# 15-DPLL_2.net
KiCad netlist of a schematic drawn in Altium Designer
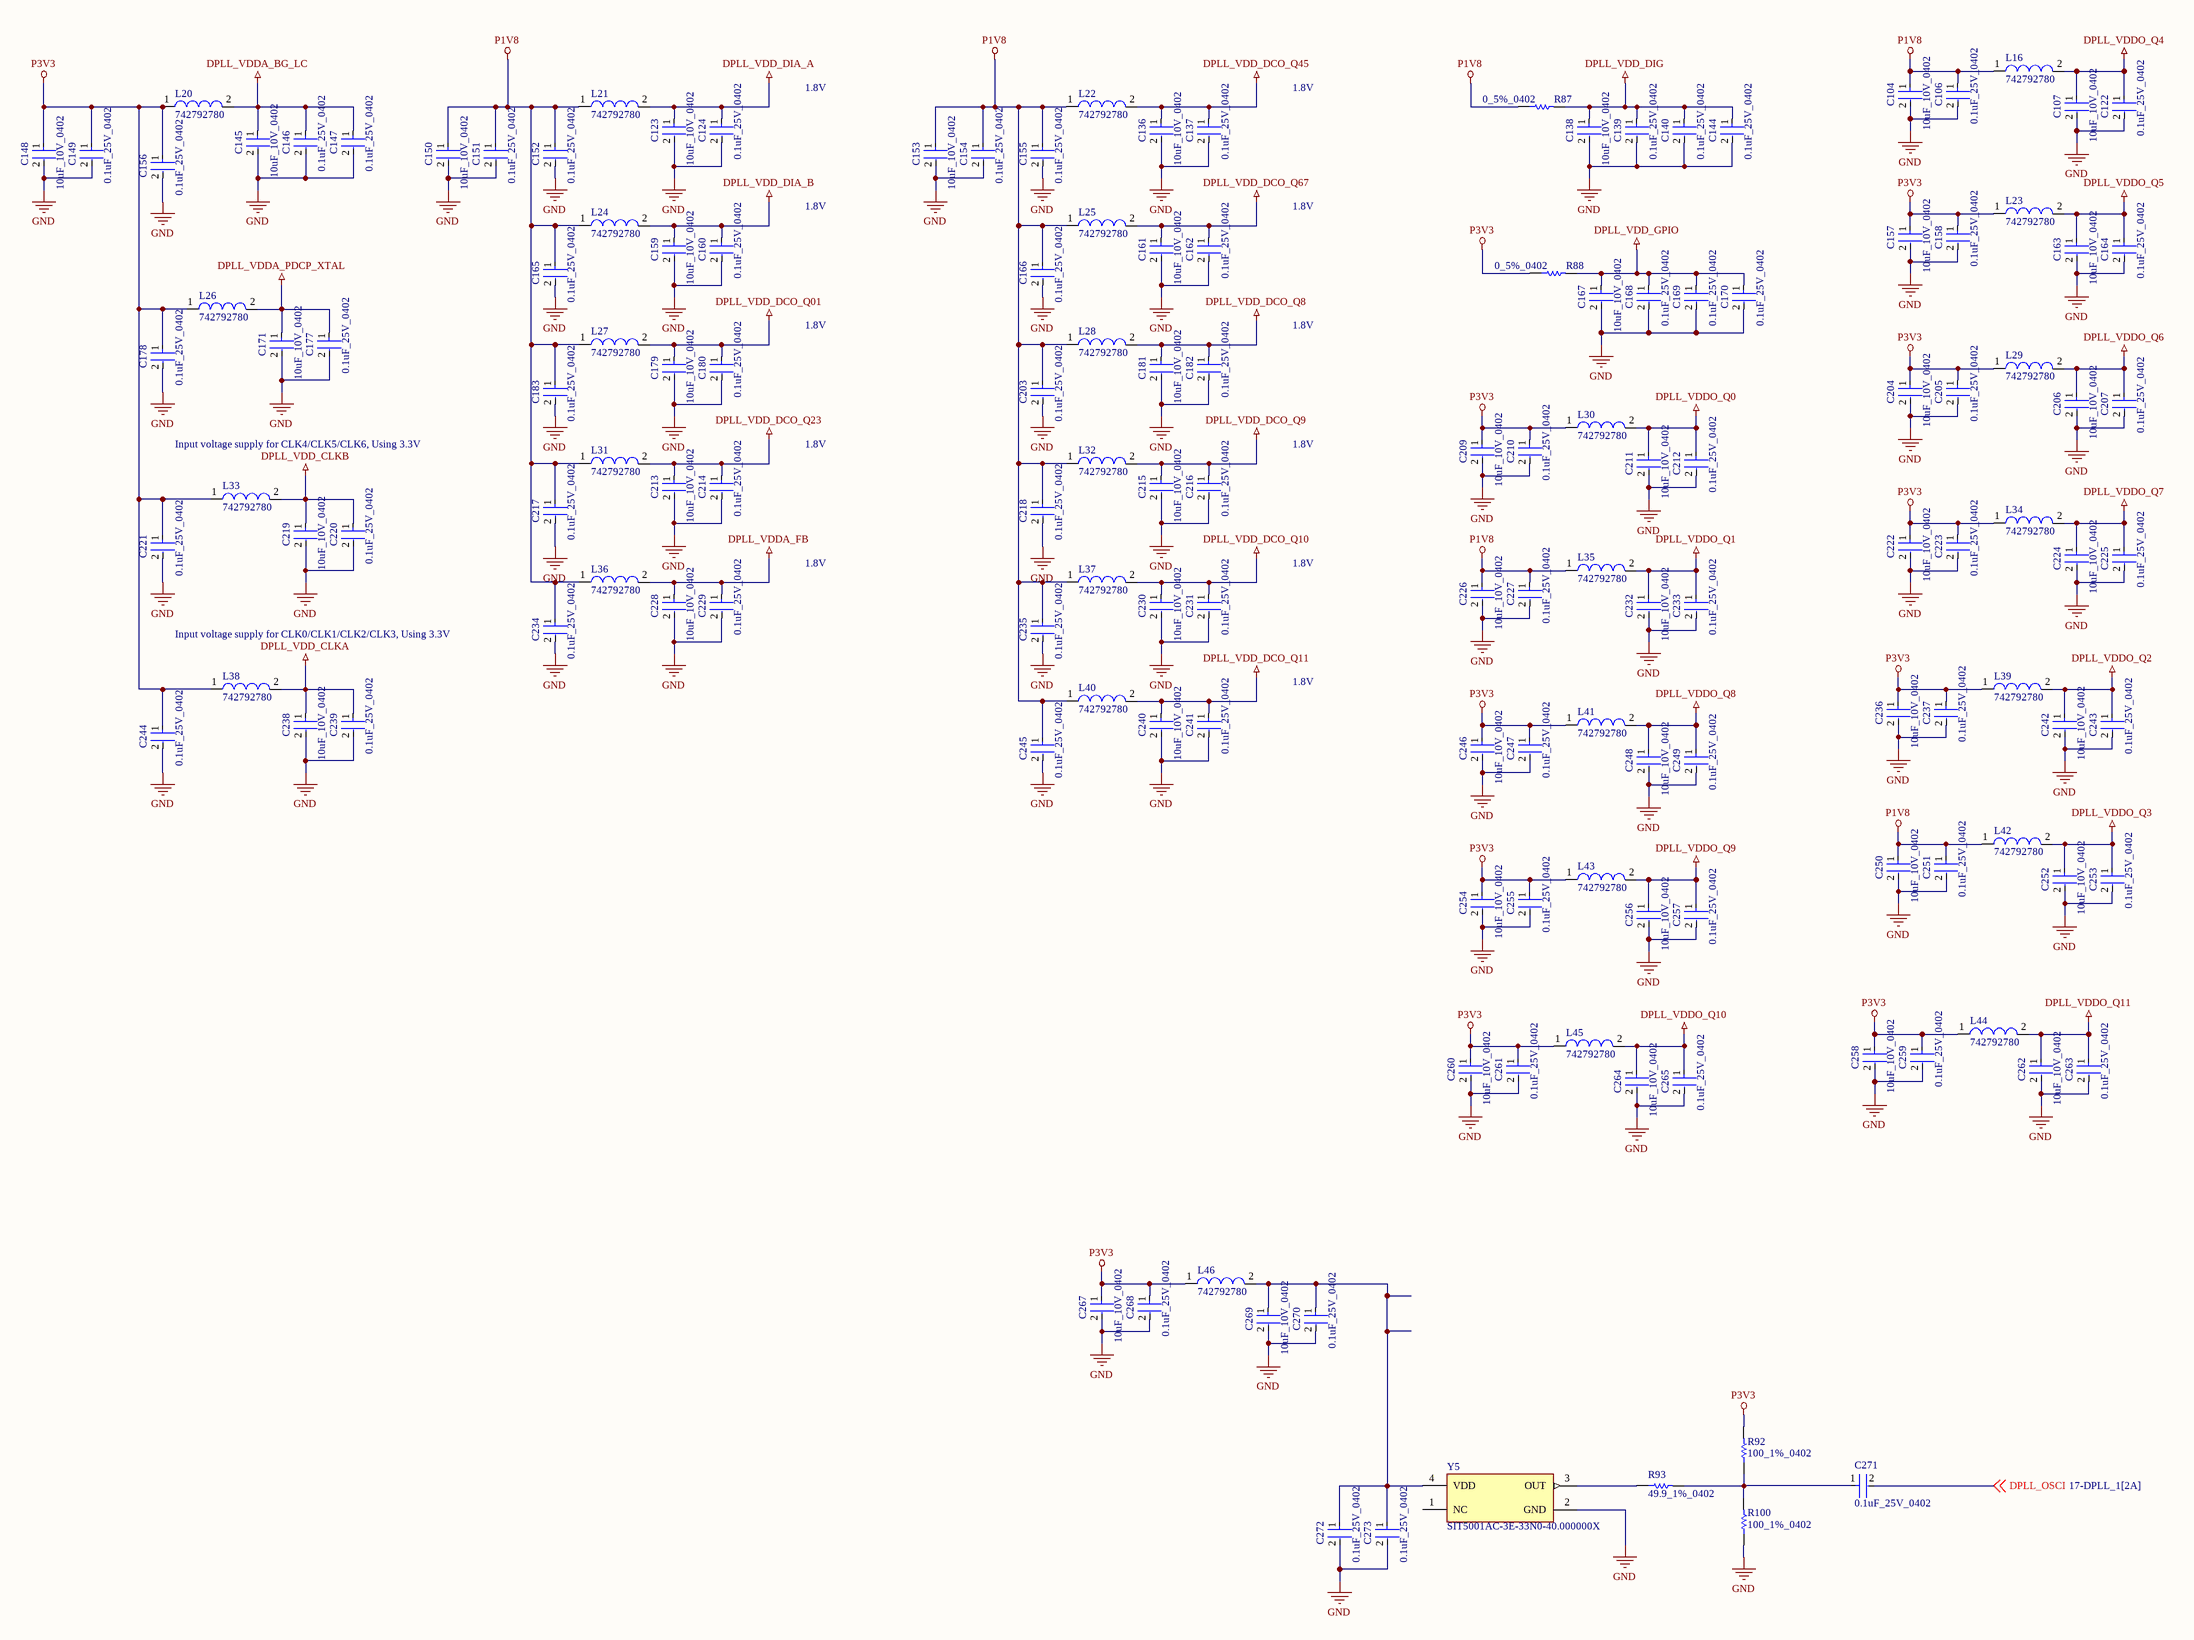
[diagram p0: 15-DPLL_2.SchDoc]

(export (version "E")
  (design (tool "Eeschema 10.0.6"))
  (components
    (comp (ref "C104")
      (value "10uF_10V_0402")
      (footprint "FP-CL05A106MP5NUNC-MFG")
      (description "CAP CER 10UF 10V X5R 0402")
      (fields
        (field (name "OCTOPART") "https://octopart.com/cl05a106mp5nunc-samsung-22457395")
        (field (name "TOLERANCE") "20%")
      )
      (libsource (lib "Altium Content Vault") (part "b4654b650e69147ec39a6b967a45e02"))
    )
    (comp (ref "C106")
      (value "0.1uF_25V_0402")
      (footprint "FP-0402-L_1_0_1-W_0_5_0_1-IPC_C")
      (description "General Purpose Ceramic Capacitor, 0402, 100nF, 10%, X7R, 15%, 25V")
      (fields (field (name "VOLTAGE") "25V") (field (name "TOLERANCE") "10%"))
      (libsource (lib "Altium Content Vault") (part "b4654b650e69147ec39a6b967a45e02"))
    )
    (comp (ref "C107")
      (value "10uF_10V_0402")
      (footprint "FP-CL05A106MP5NUNC-MFG")
      (description "CAP CER 10UF 10V X5R 0402")
      (fields
        (field (name "OCTOPART") "https://octopart.com/cl05a106mp5nunc-samsung-22457395")
        (field (name "TOLERANCE") "20%")
      )
      (libsource (lib "Altium Content Vault") (part "b4654b650e69147ec39a6b967a45e02"))
    )
    (comp (ref "C122")
      (value "0.1uF_25V_0402")
      (footprint "FP-0402-L_1_0_1-W_0_5_0_1-IPC_C")
      (description "General Purpose Ceramic Capacitor, 0402, 100nF, 10%, X7R, 15%, 25V")
      (fields (field (name "VOLTAGE") "25V") (field (name "TOLERANCE") "10%"))
      (libsource (lib "Altium Content Vault") (part "b4654b650e69147ec39a6b967a45e02"))
    )
    (comp (ref "C123")
      (value "10uF_10V_0402")
      (footprint "FP-CL05A106MP5NUNC-MFG")
      (description "CAP CER 10UF 10V X5R 0402")
      (fields
        (field (name "OCTOPART") "https://octopart.com/cl05a106mp5nunc-samsung-22457395")
        (field (name "TOLERANCE") "20%")
      )
      (libsource (lib "Altium Content Vault") (part "b4654b650e69147ec39a6b967a45e02"))
    )
    (comp (ref "C124")
      (value "0.1uF_25V_0402")
      (footprint "FP-0402-L_1_0_1-W_0_5_0_1-IPC_C")
      (description "General Purpose Ceramic Capacitor, 0402, 100nF, 10%, X7R, 15%, 25V")
      (fields (field (name "VOLTAGE") "25V") (field (name "TOLERANCE") "10%"))
      (libsource (lib "Altium Content Vault") (part "b4654b650e69147ec39a6b967a45e02"))
    )
    (comp (ref "C136")
      (value "10uF_10V_0402")
      (footprint "FP-CL05A106MP5NUNC-MFG")
      (description "CAP CER 10UF 10V X5R 0402")
      (fields
        (field (name "OCTOPART") "https://octopart.com/cl05a106mp5nunc-samsung-22457395")
        (field (name "TOLERANCE") "20%")
      )
      (libsource (lib "Altium Content Vault") (part "b4654b650e69147ec39a6b967a45e02"))
    )
    (comp (ref "C137")
      (value "0.1uF_25V_0402")
      (footprint "FP-0402-L_1_0_1-W_0_5_0_1-IPC_C")
      (description "General Purpose Ceramic Capacitor, 0402, 100nF, 10%, X7R, 15%, 25V")
      (fields (field (name "VOLTAGE") "25V") (field (name "TOLERANCE") "10%"))
      (libsource (lib "Altium Content Vault") (part "b4654b650e69147ec39a6b967a45e02"))
    )
    (comp (ref "C138")
      (value "10uF_10V_0402")
      (footprint "FP-CL05A106MP5NUNC-MFG")
      (description "CAP CER 10UF 10V X5R 0402")
      (fields
        (field (name "OCTOPART") "https://octopart.com/cl05a106mp5nunc-samsung-22457395")
        (field (name "TOLERANCE") "20%")
      )
      (libsource (lib "Altium Content Vault") (part "b4654b650e69147ec39a6b967a45e02"))
    )
    (comp (ref "C139")
      (value "0.1uF_25V_0402")
      (footprint "FP-0402-L_1_0_1-W_0_5_0_1-IPC_C")
      (description "General Purpose Ceramic Capacitor, 0402, 100nF, 10%, X7R, 15%, 25V")
      (fields (field (name "VOLTAGE") "25V") (field (name "TOLERANCE") "10%"))
      (libsource (lib "Altium Content Vault") (part "b4654b650e69147ec39a6b967a45e02"))
    )
    (comp (ref "C140")
      (value "0.1uF_25V_0402")
      (footprint "FP-0402-L_1_0_1-W_0_5_0_1-IPC_C")
      (description "General Purpose Ceramic Capacitor, 0402, 100nF, 10%, X7R, 15%, 25V")
      (fields (field (name "VOLTAGE") "25V") (field (name "TOLERANCE") "10%"))
      (libsource (lib "Altium Content Vault") (part "b4654b650e69147ec39a6b967a45e02"))
    )
    (comp (ref "C144")
      (value "0.1uF_25V_0402")
      (footprint "FP-0402-L_1_0_1-W_0_5_0_1-IPC_C")
      (description "General Purpose Ceramic Capacitor, 0402, 100nF, 10%, X7R, 15%, 25V")
      (fields (field (name "VOLTAGE") "25V") (field (name "TOLERANCE") "10%"))
      (libsource (lib "Altium Content Vault") (part "b4654b650e69147ec39a6b967a45e02"))
    )
    (comp (ref "C145")
      (value "10uF_10V_0402")
      (footprint "FP-CL05A106MP5NUNC-MFG")
      (description "CAP CER 10UF 10V X5R 0402")
      (fields
        (field (name "OCTOPART") "https://octopart.com/cl05a106mp5nunc-samsung-22457395")
        (field (name "TOLERANCE") "20%")
      )
      (libsource (lib "Altium Content Vault") (part "b4654b650e69147ec39a6b967a45e02"))
    )
    (comp (ref "C146")
      (value "0.1uF_25V_0402")
      (footprint "FP-0402-L_1_0_1-W_0_5_0_1-IPC_C")
      (description "General Purpose Ceramic Capacitor, 0402, 100nF, 10%, X7R, 15%, 25V")
      (fields (field (name "VOLTAGE") "25V") (field (name "TOLERANCE") "10%"))
      (libsource (lib "Altium Content Vault") (part "b4654b650e69147ec39a6b967a45e02"))
    )
    (comp (ref "C147")
      (value "0.1uF_25V_0402")
      (footprint "FP-0402-L_1_0_1-W_0_5_0_1-IPC_C")
      (description "General Purpose Ceramic Capacitor, 0402, 100nF, 10%, X7R, 15%, 25V")
      (fields (field (name "VOLTAGE") "25V") (field (name "TOLERANCE") "10%"))
      (libsource (lib "Altium Content Vault") (part "b4654b650e69147ec39a6b967a45e02"))
    )
    (comp (ref "C148")
      (value "10uF_10V_0402")
      (footprint "FP-CL05A106MP5NUNC-MFG")
      (description "CAP CER 10UF 10V X5R 0402")
      (fields
        (field (name "OCTOPART") "https://octopart.com/cl05a106mp5nunc-samsung-22457395")
        (field (name "TOLERANCE") "20%")
      )
      (libsource (lib "Altium Content Vault") (part "b4654b650e69147ec39a6b967a45e02"))
    )
    (comp (ref "C149")
      (value "0.1uF_25V_0402")
      (footprint "FP-0402-L_1_0_1-W_0_5_0_1-IPC_C")
      (description "General Purpose Ceramic Capacitor, 0402, 100nF, 10%, X7R, 15%, 25V")
      (fields (field (name "VOLTAGE") "25V") (field (name "TOLERANCE") "10%"))
      (libsource (lib "Altium Content Vault") (part "b4654b650e69147ec39a6b967a45e02"))
    )
    (comp (ref "C150")
      (value "10uF_10V_0402")
      (footprint "FP-CL05A106MP5NUNC-MFG")
      (description "CAP CER 10UF 10V X5R 0402")
      (fields
        (field (name "OCTOPART") "https://octopart.com/cl05a106mp5nunc-samsung-22457395")
        (field (name "TOLERANCE") "20%")
      )
      (libsource (lib "Altium Content Vault") (part "b4654b650e69147ec39a6b967a45e02"))
    )
    (comp (ref "C151")
      (value "0.1uF_25V_0402")
      (footprint "FP-0402-L_1_0_1-W_0_5_0_1-IPC_C")
      (description "General Purpose Ceramic Capacitor, 0402, 100nF, 10%, X7R, 15%, 25V")
      (fields (field (name "VOLTAGE") "25V") (field (name "TOLERANCE") "10%"))
      (libsource (lib "Altium Content Vault") (part "b4654b650e69147ec39a6b967a45e02"))
    )
    (comp (ref "C152")
      (value "0.1uF_25V_0402")
      (footprint "FP-0402-L_1_0_1-W_0_5_0_1-IPC_C")
      (description "General Purpose Ceramic Capacitor, 0402, 100nF, 10%, X7R, 15%, 25V")
      (fields (field (name "VOLTAGE") "25V") (field (name "TOLERANCE") "10%"))
      (libsource (lib "Altium Content Vault") (part "b4654b650e69147ec39a6b967a45e02"))
    )
    (comp (ref "C153")
      (value "10uF_10V_0402")
      (footprint "FP-CL05A106MP5NUNC-MFG")
      (description "CAP CER 10UF 10V X5R 0402")
      (fields
        (field (name "OCTOPART") "https://octopart.com/cl05a106mp5nunc-samsung-22457395")
        (field (name "TOLERANCE") "20%")
      )
      (libsource (lib "Altium Content Vault") (part "b4654b650e69147ec39a6b967a45e02"))
    )
    (comp (ref "C154")
      (value "0.1uF_25V_0402")
      (footprint "FP-0402-L_1_0_1-W_0_5_0_1-IPC_C")
      (description "General Purpose Ceramic Capacitor, 0402, 100nF, 10%, X7R, 15%, 25V")
      (fields (field (name "VOLTAGE") "25V") (field (name "TOLERANCE") "10%"))
      (libsource (lib "Altium Content Vault") (part "b4654b650e69147ec39a6b967a45e02"))
    )
    (comp (ref "C155")
      (value "0.1uF_25V_0402")
      (footprint "FP-0402-L_1_0_1-W_0_5_0_1-IPC_C")
      (description "General Purpose Ceramic Capacitor, 0402, 100nF, 10%, X7R, 15%, 25V")
      (fields (field (name "VOLTAGE") "25V") (field (name "TOLERANCE") "10%"))
      (libsource (lib "Altium Content Vault") (part "b4654b650e69147ec39a6b967a45e02"))
    )
    (comp (ref "C156")
      (value "0.1uF_25V_0402")
      (footprint "FP-0402-L_1_0_1-W_0_5_0_1-IPC_C")
      (description "General Purpose Ceramic Capacitor, 0402, 100nF, 10%, X7R, 15%, 25V")
      (fields (field (name "VOLTAGE") "25V") (field (name "TOLERANCE") "10%"))
      (libsource (lib "Altium Content Vault") (part "b4654b650e69147ec39a6b967a45e02"))
    )
    (comp (ref "C157")
      (value "10uF_10V_0402")
      (footprint "FP-CL05A106MP5NUNC-MFG")
      (description "CAP CER 10UF 10V X5R 0402")
      (fields
        (field (name "OCTOPART") "https://octopart.com/cl05a106mp5nunc-samsung-22457395")
        (field (name "TOLERANCE") "20%")
      )
      (libsource (lib "Altium Content Vault") (part "b4654b650e69147ec39a6b967a45e02"))
    )
    (comp (ref "C158")
      (value "0.1uF_25V_0402")
      (footprint "FP-0402-L_1_0_1-W_0_5_0_1-IPC_C")
      (description "General Purpose Ceramic Capacitor, 0402, 100nF, 10%, X7R, 15%, 25V")
      (fields (field (name "VOLTAGE") "25V") (field (name "TOLERANCE") "10%"))
      (libsource (lib "Altium Content Vault") (part "b4654b650e69147ec39a6b967a45e02"))
    )
    (comp (ref "C159")
      (value "10uF_10V_0402")
      (footprint "FP-CL05A106MP5NUNC-MFG")
      (description "CAP CER 10UF 10V X5R 0402")
      (fields
        (field (name "OCTOPART") "https://octopart.com/cl05a106mp5nunc-samsung-22457395")
        (field (name "TOLERANCE") "20%")
      )
      (libsource (lib "Altium Content Vault") (part "b4654b650e69147ec39a6b967a45e02"))
    )
    (comp (ref "C160")
      (value "0.1uF_25V_0402")
      (footprint "FP-0402-L_1_0_1-W_0_5_0_1-IPC_C")
      (description "General Purpose Ceramic Capacitor, 0402, 100nF, 10%, X7R, 15%, 25V")
      (fields (field (name "VOLTAGE") "25V") (field (name "TOLERANCE") "10%"))
      (libsource (lib "Altium Content Vault") (part "b4654b650e69147ec39a6b967a45e02"))
    )
    (comp (ref "C161")
      (value "10uF_10V_0402")
      (footprint "FP-CL05A106MP5NUNC-MFG")
      (description "CAP CER 10UF 10V X5R 0402")
      (fields
        (field (name "OCTOPART") "https://octopart.com/cl05a106mp5nunc-samsung-22457395")
        (field (name "TOLERANCE") "20%")
      )
      (libsource (lib "Altium Content Vault") (part "b4654b650e69147ec39a6b967a45e02"))
    )
    (comp (ref "C162")
      (value "0.1uF_25V_0402")
      (footprint "FP-0402-L_1_0_1-W_0_5_0_1-IPC_C")
      (description "General Purpose Ceramic Capacitor, 0402, 100nF, 10%, X7R, 15%, 25V")
      (fields (field (name "VOLTAGE") "25V") (field (name "TOLERANCE") "10%"))
      (libsource (lib "Altium Content Vault") (part "b4654b650e69147ec39a6b967a45e02"))
    )
    (comp (ref "C163")
      (value "10uF_10V_0402")
      (footprint "FP-CL05A106MP5NUNC-MFG")
      (description "CAP CER 10UF 10V X5R 0402")
      (fields
        (field (name "OCTOPART") "https://octopart.com/cl05a106mp5nunc-samsung-22457395")
        (field (name "TOLERANCE") "20%")
      )
      (libsource (lib "Altium Content Vault") (part "b4654b650e69147ec39a6b967a45e02"))
    )
    (comp (ref "C164")
      (value "0.1uF_25V_0402")
      (footprint "FP-0402-L_1_0_1-W_0_5_0_1-IPC_C")
      (description "General Purpose Ceramic Capacitor, 0402, 100nF, 10%, X7R, 15%, 25V")
      (fields (field (name "VOLTAGE") "25V") (field (name "TOLERANCE") "10%"))
      (libsource (lib "Altium Content Vault") (part "b4654b650e69147ec39a6b967a45e02"))
    )
    (comp (ref "C165")
      (value "0.1uF_25V_0402")
      (footprint "FP-0402-L_1_0_1-W_0_5_0_1-IPC_C")
      (description "General Purpose Ceramic Capacitor, 0402, 100nF, 10%, X7R, 15%, 25V")
      (fields (field (name "VOLTAGE") "25V") (field (name "TOLERANCE") "10%"))
      (libsource (lib "Altium Content Vault") (part "b4654b650e69147ec39a6b967a45e02"))
    )
    (comp (ref "C166")
      (value "0.1uF_25V_0402")
      (footprint "FP-0402-L_1_0_1-W_0_5_0_1-IPC_C")
      (description "General Purpose Ceramic Capacitor, 0402, 100nF, 10%, X7R, 15%, 25V")
      (fields (field (name "VOLTAGE") "25V") (field (name "TOLERANCE") "10%"))
      (libsource (lib "Altium Content Vault") (part "b4654b650e69147ec39a6b967a45e02"))
    )
    (comp (ref "C167")
      (value "10uF_10V_0402")
      (footprint "FP-CL05A106MP5NUNC-MFG")
      (description "CAP CER 10UF 10V X5R 0402")
      (fields
        (field (name "OCTOPART") "https://octopart.com/cl05a106mp5nunc-samsung-22457395")
        (field (name "TOLERANCE") "20%")
      )
      (libsource (lib "Altium Content Vault") (part "b4654b650e69147ec39a6b967a45e02"))
    )
    (comp (ref "C168")
      (value "0.1uF_25V_0402")
      (footprint "FP-0402-L_1_0_1-W_0_5_0_1-IPC_C")
      (description "General Purpose Ceramic Capacitor, 0402, 100nF, 10%, X7R, 15%, 25V")
      (fields (field (name "VOLTAGE") "25V") (field (name "TOLERANCE") "10%"))
      (libsource (lib "Altium Content Vault") (part "b4654b650e69147ec39a6b967a45e02"))
    )
    (comp (ref "C169")
      (value "0.1uF_25V_0402")
      (footprint "FP-0402-L_1_0_1-W_0_5_0_1-IPC_C")
      (description "General Purpose Ceramic Capacitor, 0402, 100nF, 10%, X7R, 15%, 25V")
      (fields (field (name "VOLTAGE") "25V") (field (name "TOLERANCE") "10%"))
      (libsource (lib "Altium Content Vault") (part "b4654b650e69147ec39a6b967a45e02"))
    )
    (comp (ref "C170")
      (value "0.1uF_25V_0402")
      (footprint "FP-0402-L_1_0_1-W_0_5_0_1-IPC_C")
      (description "General Purpose Ceramic Capacitor, 0402, 100nF, 10%, X7R, 15%, 25V")
      (fields (field (name "VOLTAGE") "25V") (field (name "TOLERANCE") "10%"))
      (libsource (lib "Altium Content Vault") (part "b4654b650e69147ec39a6b967a45e02"))
    )
    (comp (ref "C171")
      (value "10uF_10V_0402")
      (footprint "FP-CL05A106MP5NUNC-MFG")
      (description "CAP CER 10UF 10V X5R 0402")
      (fields
        (field (name "OCTOPART") "https://octopart.com/cl05a106mp5nunc-samsung-22457395")
        (field (name "TOLERANCE") "20%")
      )
      (libsource (lib "Altium Content Vault") (part "b4654b650e69147ec39a6b967a45e02"))
    )
    (comp (ref "C177")
      (value "0.1uF_25V_0402")
      (footprint "FP-0402-L_1_0_1-W_0_5_0_1-IPC_C")
      (description "General Purpose Ceramic Capacitor, 0402, 100nF, 10%, X7R, 15%, 25V")
      (fields (field (name "VOLTAGE") "25V") (field (name "TOLERANCE") "10%"))
      (libsource (lib "Altium Content Vault") (part "b4654b650e69147ec39a6b967a45e02"))
    )
    (comp (ref "C178")
      (value "0.1uF_25V_0402")
      (footprint "FP-0402-L_1_0_1-W_0_5_0_1-IPC_C")
      (description "General Purpose Ceramic Capacitor, 0402, 100nF, 10%, X7R, 15%, 25V")
      (fields (field (name "VOLTAGE") "25V") (field (name "TOLERANCE") "10%"))
      (libsource (lib "Altium Content Vault") (part "b4654b650e69147ec39a6b967a45e02"))
    )
    (comp (ref "C179")
      (value "10uF_10V_0402")
      (footprint "FP-CL05A106MP5NUNC-MFG")
      (description "CAP CER 10UF 10V X5R 0402")
      (fields
        (field (name "OCTOPART") "https://octopart.com/cl05a106mp5nunc-samsung-22457395")
        (field (name "TOLERANCE") "20%")
      )
      (libsource (lib "Altium Content Vault") (part "b4654b650e69147ec39a6b967a45e02"))
    )
    (comp (ref "C180")
      (value "0.1uF_25V_0402")
      (footprint "FP-0402-L_1_0_1-W_0_5_0_1-IPC_C")
      (description "General Purpose Ceramic Capacitor, 0402, 100nF, 10%, X7R, 15%, 25V")
      (fields (field (name "VOLTAGE") "25V") (field (name "TOLERANCE") "10%"))
      (libsource (lib "Altium Content Vault") (part "b4654b650e69147ec39a6b967a45e02"))
    )
    (comp (ref "C181")
      (value "10uF_10V_0402")
      (footprint "FP-CL05A106MP5NUNC-MFG")
      (description "CAP CER 10UF 10V X5R 0402")
      (fields
        (field (name "OCTOPART") "https://octopart.com/cl05a106mp5nunc-samsung-22457395")
        (field (name "TOLERANCE") "20%")
      )
      (libsource (lib "Altium Content Vault") (part "b4654b650e69147ec39a6b967a45e02"))
    )
    (comp (ref "C182")
      (value "0.1uF_25V_0402")
      (footprint "FP-0402-L_1_0_1-W_0_5_0_1-IPC_C")
      (description "General Purpose Ceramic Capacitor, 0402, 100nF, 10%, X7R, 15%, 25V")
      (fields (field (name "VOLTAGE") "25V") (field (name "TOLERANCE") "10%"))
      (libsource (lib "Altium Content Vault") (part "b4654b650e69147ec39a6b967a45e02"))
    )
    (comp (ref "C183")
      (value "0.1uF_25V_0402")
      (footprint "FP-0402-L_1_0_1-W_0_5_0_1-IPC_C")
      (description "General Purpose Ceramic Capacitor, 0402, 100nF, 10%, X7R, 15%, 25V")
      (fields (field (name "VOLTAGE") "25V") (field (name "TOLERANCE") "10%"))
      (libsource (lib "Altium Content Vault") (part "b4654b650e69147ec39a6b967a45e02"))
    )
    (comp (ref "C203")
      (value "0.1uF_25V_0402")
      (footprint "FP-0402-L_1_0_1-W_0_5_0_1-IPC_C")
      (description "General Purpose Ceramic Capacitor, 0402, 100nF, 10%, X7R, 15%, 25V")
      (fields (field (name "VOLTAGE") "25V") (field (name "TOLERANCE") "10%"))
      (libsource (lib "Altium Content Vault") (part "b4654b650e69147ec39a6b967a45e02"))
    )
    (comp (ref "C204")
      (value "10uF_10V_0402")
      (footprint "FP-CL05A106MP5NUNC-MFG")
      (description "CAP CER 10UF 10V X5R 0402")
      (fields
        (field (name "OCTOPART") "https://octopart.com/cl05a106mp5nunc-samsung-22457395")
        (field (name "TOLERANCE") "20%")
      )
      (libsource (lib "Altium Content Vault") (part "b4654b650e69147ec39a6b967a45e02"))
    )
    (comp (ref "C205")
      (value "0.1uF_25V_0402")
      (footprint "FP-0402-L_1_0_1-W_0_5_0_1-IPC_C")
      (description "General Purpose Ceramic Capacitor, 0402, 100nF, 10%, X7R, 15%, 25V")
      (fields (field (name "VOLTAGE") "25V") (field (name "TOLERANCE") "10%"))
      (libsource (lib "Altium Content Vault") (part "b4654b650e69147ec39a6b967a45e02"))
    )
    (comp (ref "C206")
      (value "10uF_10V_0402")
      (footprint "FP-CL05A106MP5NUNC-MFG")
      (description "CAP CER 10UF 10V X5R 0402")
      (fields
        (field (name "OCTOPART") "https://octopart.com/cl05a106mp5nunc-samsung-22457395")
        (field (name "TOLERANCE") "20%")
      )
      (libsource (lib "Altium Content Vault") (part "b4654b650e69147ec39a6b967a45e02"))
    )
    (comp (ref "C207")
      (value "0.1uF_25V_0402")
      (footprint "FP-0402-L_1_0_1-W_0_5_0_1-IPC_C")
      (description "General Purpose Ceramic Capacitor, 0402, 100nF, 10%, X7R, 15%, 25V")
      (fields (field (name "VOLTAGE") "25V") (field (name "TOLERANCE") "10%"))
      (libsource (lib "Altium Content Vault") (part "b4654b650e69147ec39a6b967a45e02"))
    )
    (comp (ref "C209")
      (value "10uF_10V_0402")
      (footprint "FP-CL05A106MP5NUNC-MFG")
      (description "CAP CER 10UF 10V X5R 0402")
      (fields
        (field (name "OCTOPART") "https://octopart.com/cl05a106mp5nunc-samsung-22457395")
        (field (name "TOLERANCE") "20%")
      )
      (libsource (lib "Altium Content Vault") (part "b4654b650e69147ec39a6b967a45e02"))
    )
    (comp (ref "C210")
      (value "0.1uF_25V_0402")
      (footprint "FP-0402-L_1_0_1-W_0_5_0_1-IPC_C")
      (description "General Purpose Ceramic Capacitor, 0402, 100nF, 10%, X7R, 15%, 25V")
      (fields (field (name "VOLTAGE") "25V") (field (name "TOLERANCE") "10%"))
      (libsource (lib "Altium Content Vault") (part "b4654b650e69147ec39a6b967a45e02"))
    )
    (comp (ref "C211")
      (value "10uF_10V_0402")
      (footprint "FP-CL05A106MP5NUNC-MFG")
      (description "CAP CER 10UF 10V X5R 0402")
      (fields
        (field (name "OCTOPART") "https://octopart.com/cl05a106mp5nunc-samsung-22457395")
        (field (name "TOLERANCE") "20%")
      )
      (libsource (lib "Altium Content Vault") (part "b4654b650e69147ec39a6b967a45e02"))
    )
    (comp (ref "C212")
      (value "0.1uF_25V_0402")
      (footprint "FP-0402-L_1_0_1-W_0_5_0_1-IPC_C")
      (description "General Purpose Ceramic Capacitor, 0402, 100nF, 10%, X7R, 15%, 25V")
      (fields (field (name "VOLTAGE") "25V") (field (name "TOLERANCE") "10%"))
      (libsource (lib "Altium Content Vault") (part "b4654b650e69147ec39a6b967a45e02"))
    )
    (comp (ref "C213")
      (value "10uF_10V_0402")
      (footprint "FP-CL05A106MP5NUNC-MFG")
      (description "CAP CER 10UF 10V X5R 0402")
      (fields
        (field (name "OCTOPART") "https://octopart.com/cl05a106mp5nunc-samsung-22457395")
        (field (name "TOLERANCE") "20%")
      )
      (libsource (lib "Altium Content Vault") (part "b4654b650e69147ec39a6b967a45e02"))
    )
    (comp (ref "C214")
      (value "0.1uF_25V_0402")
      (footprint "FP-0402-L_1_0_1-W_0_5_0_1-IPC_C")
      (description "General Purpose Ceramic Capacitor, 0402, 100nF, 10%, X7R, 15%, 25V")
      (fields (field (name "VOLTAGE") "25V") (field (name "TOLERANCE") "10%"))
      (libsource (lib "Altium Content Vault") (part "b4654b650e69147ec39a6b967a45e02"))
    )
    (comp (ref "C215")
      (value "10uF_10V_0402")
      (footprint "FP-CL05A106MP5NUNC-MFG")
      (description "CAP CER 10UF 10V X5R 0402")
      (fields
        (field (name "OCTOPART") "https://octopart.com/cl05a106mp5nunc-samsung-22457395")
        (field (name "TOLERANCE") "20%")
      )
      (libsource (lib "Altium Content Vault") (part "b4654b650e69147ec39a6b967a45e02"))
    )
    (comp (ref "C216")
      (value "0.1uF_25V_0402")
      (footprint "FP-0402-L_1_0_1-W_0_5_0_1-IPC_C")
      (description "General Purpose Ceramic Capacitor, 0402, 100nF, 10%, X7R, 15%, 25V")
      (fields (field (name "VOLTAGE") "25V") (field (name "TOLERANCE") "10%"))
      (libsource (lib "Altium Content Vault") (part "b4654b650e69147ec39a6b967a45e02"))
    )
    (comp (ref "C217")
      (value "0.1uF_25V_0402")
      (footprint "FP-0402-L_1_0_1-W_0_5_0_1-IPC_C")
      (description "General Purpose Ceramic Capacitor, 0402, 100nF, 10%, X7R, 15%, 25V")
      (fields (field (name "VOLTAGE") "25V") (field (name "TOLERANCE") "10%"))
      (libsource (lib "Altium Content Vault") (part "b4654b650e69147ec39a6b967a45e02"))
    )
    (comp (ref "C218")
      (value "0.1uF_25V_0402")
      (footprint "FP-0402-L_1_0_1-W_0_5_0_1-IPC_C")
      (description "General Purpose Ceramic Capacitor, 0402, 100nF, 10%, X7R, 15%, 25V")
      (fields (field (name "VOLTAGE") "25V") (field (name "TOLERANCE") "10%"))
      (libsource (lib "Altium Content Vault") (part "b4654b650e69147ec39a6b967a45e02"))
    )
    (comp (ref "C219")
      (value "10uF_10V_0402")
      (footprint "FP-CL05A106MP5NUNC-MFG")
      (description "CAP CER 10UF 10V X5R 0402")
      (fields
        (field (name "OCTOPART") "https://octopart.com/cl05a106mp5nunc-samsung-22457395")
        (field (name "TOLERANCE") "20%")
      )
      (libsource (lib "Altium Content Vault") (part "b4654b650e69147ec39a6b967a45e02"))
    )
    (comp (ref "C220")
      (value "0.1uF_25V_0402")
      (footprint "FP-0402-L_1_0_1-W_0_5_0_1-IPC_C")
      (description "General Purpose Ceramic Capacitor, 0402, 100nF, 10%, X7R, 15%, 25V")
      (fields (field (name "VOLTAGE") "25V") (field (name "TOLERANCE") "10%"))
      (libsource (lib "Altium Content Vault") (part "b4654b650e69147ec39a6b967a45e02"))
    )
    (comp (ref "C221")
      (value "0.1uF_25V_0402")
      (footprint "FP-0402-L_1_0_1-W_0_5_0_1-IPC_C")
      (description "General Purpose Ceramic Capacitor, 0402, 100nF, 10%, X7R, 15%, 25V")
      (fields (field (name "VOLTAGE") "25V") (field (name "TOLERANCE") "10%"))
      (libsource (lib "Altium Content Vault") (part "b4654b650e69147ec39a6b967a45e02"))
    )
    (comp (ref "C222")
      (value "10uF_10V_0402")
      (footprint "FP-CL05A106MP5NUNC-MFG")
      (description "CAP CER 10UF 10V X5R 0402")
      (fields
        (field (name "OCTOPART") "https://octopart.com/cl05a106mp5nunc-samsung-22457395")
        (field (name "TOLERANCE") "20%")
      )
      (libsource (lib "Altium Content Vault") (part "b4654b650e69147ec39a6b967a45e02"))
    )
    (comp (ref "C223")
      (value "0.1uF_25V_0402")
      (footprint "FP-0402-L_1_0_1-W_0_5_0_1-IPC_C")
      (description "General Purpose Ceramic Capacitor, 0402, 100nF, 10%, X7R, 15%, 25V")
      (fields (field (name "VOLTAGE") "25V") (field (name "TOLERANCE") "10%"))
      (libsource (lib "Altium Content Vault") (part "b4654b650e69147ec39a6b967a45e02"))
    )
    (comp (ref "C224")
      (value "10uF_10V_0402")
      (footprint "FP-CL05A106MP5NUNC-MFG")
      (description "CAP CER 10UF 10V X5R 0402")
      (fields
        (field (name "OCTOPART") "https://octopart.com/cl05a106mp5nunc-samsung-22457395")
        (field (name "TOLERANCE") "20%")
      )
      (libsource (lib "Altium Content Vault") (part "b4654b650e69147ec39a6b967a45e02"))
    )
    (comp (ref "C225")
      (value "0.1uF_25V_0402")
      (footprint "FP-0402-L_1_0_1-W_0_5_0_1-IPC_C")
      (description "General Purpose Ceramic Capacitor, 0402, 100nF, 10%, X7R, 15%, 25V")
      (fields (field (name "VOLTAGE") "25V") (field (name "TOLERANCE") "10%"))
      (libsource (lib "Altium Content Vault") (part "b4654b650e69147ec39a6b967a45e02"))
    )
    (comp (ref "C226")
      (value "10uF_10V_0402")
      (footprint "FP-CL05A106MP5NUNC-MFG")
      (description "CAP CER 10UF 10V X5R 0402")
      (fields
        (field (name "OCTOPART") "https://octopart.com/cl05a106mp5nunc-samsung-22457395")
        (field (name "TOLERANCE") "20%")
      )
      (libsource (lib "Altium Content Vault") (part "b4654b650e69147ec39a6b967a45e02"))
    )
    (comp (ref "C227")
      (value "0.1uF_25V_0402")
      (footprint "FP-0402-L_1_0_1-W_0_5_0_1-IPC_C")
      (description "General Purpose Ceramic Capacitor, 0402, 100nF, 10%, X7R, 15%, 25V")
      (fields (field (name "VOLTAGE") "25V") (field (name "TOLERANCE") "10%"))
      (libsource (lib "Altium Content Vault") (part "b4654b650e69147ec39a6b967a45e02"))
    )
    (comp (ref "C228")
      (value "10uF_10V_0402")
      (footprint "FP-CL05A106MP5NUNC-MFG")
      (description "CAP CER 10UF 10V X5R 0402")
      (fields
        (field (name "OCTOPART") "https://octopart.com/cl05a106mp5nunc-samsung-22457395")
        (field (name "TOLERANCE") "20%")
      )
      (libsource (lib "Altium Content Vault") (part "b4654b650e69147ec39a6b967a45e02"))
    )
    (comp (ref "C229")
      (value "0.1uF_25V_0402")
      (footprint "FP-0402-L_1_0_1-W_0_5_0_1-IPC_C")
      (description "General Purpose Ceramic Capacitor, 0402, 100nF, 10%, X7R, 15%, 25V")
      (fields (field (name "VOLTAGE") "25V") (field (name "TOLERANCE") "10%"))
      (libsource (lib "Altium Content Vault") (part "b4654b650e69147ec39a6b967a45e02"))
    )
    (comp (ref "C230")
      (value "10uF_10V_0402")
      (footprint "FP-CL05A106MP5NUNC-MFG")
      (description "CAP CER 10UF 10V X5R 0402")
      (fields
        (field (name "OCTOPART") "https://octopart.com/cl05a106mp5nunc-samsung-22457395")
        (field (name "TOLERANCE") "20%")
      )
      (libsource (lib "Altium Content Vault") (part "b4654b650e69147ec39a6b967a45e02"))
    )
    (comp (ref "C231")
      (value "0.1uF_25V_0402")
      (footprint "FP-0402-L_1_0_1-W_0_5_0_1-IPC_C")
      (description "General Purpose Ceramic Capacitor, 0402, 100nF, 10%, X7R, 15%, 25V")
      (fields (field (name "VOLTAGE") "25V") (field (name "TOLERANCE") "10%"))
      (libsource (lib "Altium Content Vault") (part "b4654b650e69147ec39a6b967a45e02"))
    )
    (comp (ref "C232")
      (value "10uF_10V_0402")
      (footprint "FP-CL05A106MP5NUNC-MFG")
      (description "CAP CER 10UF 10V X5R 0402")
      (fields
        (field (name "OCTOPART") "https://octopart.com/cl05a106mp5nunc-samsung-22457395")
        (field (name "TOLERANCE") "20%")
      )
      (libsource (lib "Altium Content Vault") (part "b4654b650e69147ec39a6b967a45e02"))
    )
    (comp (ref "C233")
      (value "0.1uF_25V_0402")
      (footprint "FP-0402-L_1_0_1-W_0_5_0_1-IPC_C")
      (description "General Purpose Ceramic Capacitor, 0402, 100nF, 10%, X7R, 15%, 25V")
      (fields (field (name "VOLTAGE") "25V") (field (name "TOLERANCE") "10%"))
      (libsource (lib "Altium Content Vault") (part "b4654b650e69147ec39a6b967a45e02"))
    )
    (comp (ref "C234")
      (value "0.1uF_25V_0402")
      (footprint "FP-0402-L_1_0_1-W_0_5_0_1-IPC_C")
      (description "General Purpose Ceramic Capacitor, 0402, 100nF, 10%, X7R, 15%, 25V")
      (fields (field (name "VOLTAGE") "25V") (field (name "TOLERANCE") "10%"))
      (libsource (lib "Altium Content Vault") (part "b4654b650e69147ec39a6b967a45e02"))
    )
    (comp (ref "C235")
      (value "0.1uF_25V_0402")
      (footprint "FP-0402-L_1_0_1-W_0_5_0_1-IPC_C")
      (description "General Purpose Ceramic Capacitor, 0402, 100nF, 10%, X7R, 15%, 25V")
      (fields (field (name "VOLTAGE") "25V") (field (name "TOLERANCE") "10%"))
      (libsource (lib "Altium Content Vault") (part "b4654b650e69147ec39a6b967a45e02"))
    )
    (comp (ref "C236")
      (value "10uF_10V_0402")
      (footprint "FP-CL05A106MP5NUNC-MFG")
      (description "CAP CER 10UF 10V X5R 0402")
      (fields
        (field (name "OCTOPART") "https://octopart.com/cl05a106mp5nunc-samsung-22457395")
        (field (name "TOLERANCE") "20%")
      )
      (libsource (lib "Altium Content Vault") (part "b4654b650e69147ec39a6b967a45e02"))
    )
    (comp (ref "C237")
      (value "0.1uF_25V_0402")
      (footprint "FP-0402-L_1_0_1-W_0_5_0_1-IPC_C")
      (description "General Purpose Ceramic Capacitor, 0402, 100nF, 10%, X7R, 15%, 25V")
      (fields (field (name "VOLTAGE") "25V") (field (name "TOLERANCE") "10%"))
      (libsource (lib "Altium Content Vault") (part "b4654b650e69147ec39a6b967a45e02"))
    )
    (comp (ref "C238")
      (value "10uF_10V_0402")
      (footprint "FP-CL05A106MP5NUNC-MFG")
      (description "CAP CER 10UF 10V X5R 0402")
      (fields
        (field (name "OCTOPART") "https://octopart.com/cl05a106mp5nunc-samsung-22457395")
        (field (name "TOLERANCE") "20%")
      )
      (libsource (lib "Altium Content Vault") (part "b4654b650e69147ec39a6b967a45e02"))
    )
    (comp (ref "C239")
      (value "0.1uF_25V_0402")
      (footprint "FP-0402-L_1_0_1-W_0_5_0_1-IPC_C")
      (description "General Purpose Ceramic Capacitor, 0402, 100nF, 10%, X7R, 15%, 25V")
      (fields (field (name "VOLTAGE") "25V") (field (name "TOLERANCE") "10%"))
      (libsource (lib "Altium Content Vault") (part "b4654b650e69147ec39a6b967a45e02"))
    )
    (comp (ref "C240")
      (value "10uF_10V_0402")
      (footprint "FP-CL05A106MP5NUNC-MFG")
      (description "CAP CER 10UF 10V X5R 0402")
      (fields
        (field (name "OCTOPART") "https://octopart.com/cl05a106mp5nunc-samsung-22457395")
        (field (name "TOLERANCE") "20%")
      )
      (libsource (lib "Altium Content Vault") (part "b4654b650e69147ec39a6b967a45e02"))
    )
    (comp (ref "C241")
      (value "0.1uF_25V_0402")
      (footprint "FP-0402-L_1_0_1-W_0_5_0_1-IPC_C")
      (description "General Purpose Ceramic Capacitor, 0402, 100nF, 10%, X7R, 15%, 25V")
      (fields (field (name "VOLTAGE") "25V") (field (name "TOLERANCE") "10%"))
      (libsource (lib "Altium Content Vault") (part "b4654b650e69147ec39a6b967a45e02"))
    )
    (comp (ref "C242")
      (value "10uF_10V_0402")
      (footprint "FP-CL05A106MP5NUNC-MFG")
      (description "CAP CER 10UF 10V X5R 0402")
      (fields
        (field (name "OCTOPART") "https://octopart.com/cl05a106mp5nunc-samsung-22457395")
        (field (name "TOLERANCE") "20%")
      )
      (libsource (lib "Altium Content Vault") (part "b4654b650e69147ec39a6b967a45e02"))
    )
    (comp (ref "C243")
      (value "0.1uF_25V_0402")
      (footprint "FP-0402-L_1_0_1-W_0_5_0_1-IPC_C")
      (description "General Purpose Ceramic Capacitor, 0402, 100nF, 10%, X7R, 15%, 25V")
      (fields (field (name "VOLTAGE") "25V") (field (name "TOLERANCE") "10%"))
      (libsource (lib "Altium Content Vault") (part "b4654b650e69147ec39a6b967a45e02"))
    )
    (comp (ref "C244")
      (value "0.1uF_25V_0402")
      (footprint "FP-0402-L_1_0_1-W_0_5_0_1-IPC_C")
      (description "General Purpose Ceramic Capacitor, 0402, 100nF, 10%, X7R, 15%, 25V")
      (fields (field (name "VOLTAGE") "25V") (field (name "TOLERANCE") "10%"))
      (libsource (lib "Altium Content Vault") (part "b4654b650e69147ec39a6b967a45e02"))
    )
    (comp (ref "C245")
      (value "0.1uF_25V_0402")
      (footprint "FP-0402-L_1_0_1-W_0_5_0_1-IPC_C")
      (description "General Purpose Ceramic Capacitor, 0402, 100nF, 10%, X7R, 15%, 25V")
      (fields (field (name "VOLTAGE") "25V") (field (name "TOLERANCE") "10%"))
      (libsource (lib "Altium Content Vault") (part "b4654b650e69147ec39a6b967a45e02"))
    )
    (comp (ref "C246")
      (value "10uF_10V_0402")
      (footprint "FP-CL05A106MP5NUNC-MFG")
      (description "CAP CER 10UF 10V X5R 0402")
      (fields
        (field (name "OCTOPART") "https://octopart.com/cl05a106mp5nunc-samsung-22457395")
        (field (name "TOLERANCE") "20%")
      )
      (libsource (lib "Altium Content Vault") (part "b4654b650e69147ec39a6b967a45e02"))
    )
    (comp (ref "C247")
      (value "0.1uF_25V_0402")
      (footprint "FP-0402-L_1_0_1-W_0_5_0_1-IPC_C")
      (description "General Purpose Ceramic Capacitor, 0402, 100nF, 10%, X7R, 15%, 25V")
      (fields (field (name "VOLTAGE") "25V") (field (name "TOLERANCE") "10%"))
      (libsource (lib "Altium Content Vault") (part "b4654b650e69147ec39a6b967a45e02"))
    )
    (comp (ref "C248")
      (value "10uF_10V_0402")
      (footprint "FP-CL05A106MP5NUNC-MFG")
      (description "CAP CER 10UF 10V X5R 0402")
      (fields
        (field (name "OCTOPART") "https://octopart.com/cl05a106mp5nunc-samsung-22457395")
        (field (name "TOLERANCE") "20%")
      )
      (libsource (lib "Altium Content Vault") (part "b4654b650e69147ec39a6b967a45e02"))
    )
    (comp (ref "C249")
      (value "0.1uF_25V_0402")
      (footprint "FP-0402-L_1_0_1-W_0_5_0_1-IPC_C")
      (description "General Purpose Ceramic Capacitor, 0402, 100nF, 10%, X7R, 15%, 25V")
      (fields (field (name "VOLTAGE") "25V") (field (name "TOLERANCE") "10%"))
      (libsource (lib "Altium Content Vault") (part "b4654b650e69147ec39a6b967a45e02"))
    )
    (comp (ref "C250")
      (value "10uF_10V_0402")
      (footprint "FP-CL05A106MP5NUNC-MFG")
      (description "CAP CER 10UF 10V X5R 0402")
      (fields
        (field (name "OCTOPART") "https://octopart.com/cl05a106mp5nunc-samsung-22457395")
        (field (name "TOLERANCE") "20%")
      )
      (libsource (lib "Altium Content Vault") (part "b4654b650e69147ec39a6b967a45e02"))
    )
    (comp (ref "C251")
      (value "0.1uF_25V_0402")
      (footprint "FP-0402-L_1_0_1-W_0_5_0_1-IPC_C")
      (description "General Purpose Ceramic Capacitor, 0402, 100nF, 10%, X7R, 15%, 25V")
      (fields (field (name "VOLTAGE") "25V") (field (name "TOLERANCE") "10%"))
      (libsource (lib "Altium Content Vault") (part "b4654b650e69147ec39a6b967a45e02"))
    )
    (comp (ref "C252")
      (value "10uF_10V_0402")
      (footprint "FP-CL05A106MP5NUNC-MFG")
      (description "CAP CER 10UF 10V X5R 0402")
      (fields
        (field (name "OCTOPART") "https://octopart.com/cl05a106mp5nunc-samsung-22457395")
        (field (name "TOLERANCE") "20%")
      )
      (libsource (lib "Altium Content Vault") (part "b4654b650e69147ec39a6b967a45e02"))
    )
    (comp (ref "C253")
      (value "0.1uF_25V_0402")
      (footprint "FP-0402-L_1_0_1-W_0_5_0_1-IPC_C")
      (description "General Purpose Ceramic Capacitor, 0402, 100nF, 10%, X7R, 15%, 25V")
      (fields (field (name "VOLTAGE") "25V") (field (name "TOLERANCE") "10%"))
      (libsource (lib "Altium Content Vault") (part "b4654b650e69147ec39a6b967a45e02"))
    )
    (comp (ref "C254")
      (value "10uF_10V_0402")
      (footprint "FP-CL05A106MP5NUNC-MFG")
      (description "CAP CER 10UF 10V X5R 0402")
      (fields
        (field (name "OCTOPART") "https://octopart.com/cl05a106mp5nunc-samsung-22457395")
        (field (name "TOLERANCE") "20%")
      )
      (libsource (lib "Altium Content Vault") (part "b4654b650e69147ec39a6b967a45e02"))
    )
    (comp (ref "C255")
      (value "0.1uF_25V_0402")
      (footprint "FP-0402-L_1_0_1-W_0_5_0_1-IPC_C")
      (description "General Purpose Ceramic Capacitor, 0402, 100nF, 10%, X7R, 15%, 25V")
      (fields (field (name "VOLTAGE") "25V") (field (name "TOLERANCE") "10%"))
      (libsource (lib "Altium Content Vault") (part "b4654b650e69147ec39a6b967a45e02"))
    )
    (comp (ref "C256")
      (value "10uF_10V_0402")
      (footprint "FP-CL05A106MP5NUNC-MFG")
      (description "CAP CER 10UF 10V X5R 0402")
      (fields
        (field (name "OCTOPART") "https://octopart.com/cl05a106mp5nunc-samsung-22457395")
        (field (name "TOLERANCE") "20%")
      )
      (libsource (lib "Altium Content Vault") (part "b4654b650e69147ec39a6b967a45e02"))
    )
    (comp (ref "C257")
      (value "0.1uF_25V_0402")
      (footprint "FP-0402-L_1_0_1-W_0_5_0_1-IPC_C")
      (description "General Purpose Ceramic Capacitor, 0402, 100nF, 10%, X7R, 15%, 25V")
      (fields (field (name "VOLTAGE") "25V") (field (name "TOLERANCE") "10%"))
      (libsource (lib "Altium Content Vault") (part "b4654b650e69147ec39a6b967a45e02"))
    )
    (comp (ref "C258")
      (value "10uF_10V_0402")
      (footprint "FP-CL05A106MP5NUNC-MFG")
      (description "CAP CER 10UF 10V X5R 0402")
      (fields
        (field (name "OCTOPART") "https://octopart.com/cl05a106mp5nunc-samsung-22457395")
        (field (name "TOLERANCE") "20%")
      )
      (libsource (lib "Altium Content Vault") (part "b4654b650e69147ec39a6b967a45e02"))
    )
    (comp (ref "C259")
      (value "0.1uF_25V_0402")
      (footprint "FP-0402-L_1_0_1-W_0_5_0_1-IPC_C")
      (description "General Purpose Ceramic Capacitor, 0402, 100nF, 10%, X7R, 15%, 25V")
      (fields (field (name "VOLTAGE") "25V") (field (name "TOLERANCE") "10%"))
      (libsource (lib "Altium Content Vault") (part "b4654b650e69147ec39a6b967a45e02"))
    )
    (comp (ref "C260")
      (value "10uF_10V_0402")
      (footprint "FP-CL05A106MP5NUNC-MFG")
      (description "CAP CER 10UF 10V X5R 0402")
      (fields
        (field (name "OCTOPART") "https://octopart.com/cl05a106mp5nunc-samsung-22457395")
        (field (name "TOLERANCE") "20%")
      )
      (libsource (lib "Altium Content Vault") (part "b4654b650e69147ec39a6b967a45e02"))
    )
    (comp (ref "C261")
      (value "0.1uF_25V_0402")
      (footprint "FP-0402-L_1_0_1-W_0_5_0_1-IPC_C")
      (description "General Purpose Ceramic Capacitor, 0402, 100nF, 10%, X7R, 15%, 25V")
      (fields (field (name "VOLTAGE") "25V") (field (name "TOLERANCE") "10%"))
      (libsource (lib "Altium Content Vault") (part "b4654b650e69147ec39a6b967a45e02"))
    )
    (comp (ref "C262")
      (value "10uF_10V_0402")
      (footprint "FP-CL05A106MP5NUNC-MFG")
      (description "CAP CER 10UF 10V X5R 0402")
      (fields
        (field (name "OCTOPART") "https://octopart.com/cl05a106mp5nunc-samsung-22457395")
        (field (name "TOLERANCE") "20%")
      )
      (libsource (lib "Altium Content Vault") (part "b4654b650e69147ec39a6b967a45e02"))
    )
    (comp (ref "C263")
      (value "0.1uF_25V_0402")
      (footprint "FP-0402-L_1_0_1-W_0_5_0_1-IPC_C")
      (description "General Purpose Ceramic Capacitor, 0402, 100nF, 10%, X7R, 15%, 25V")
      (fields (field (name "VOLTAGE") "25V") (field (name "TOLERANCE") "10%"))
      (libsource (lib "Altium Content Vault") (part "b4654b650e69147ec39a6b967a45e02"))
    )
    (comp (ref "C264")
      (value "10uF_10V_0402")
      (footprint "FP-CL05A106MP5NUNC-MFG")
      (description "CAP CER 10UF 10V X5R 0402")
      (fields
        (field (name "OCTOPART") "https://octopart.com/cl05a106mp5nunc-samsung-22457395")
        (field (name "TOLERANCE") "20%")
      )
      (libsource (lib "Altium Content Vault") (part "b4654b650e69147ec39a6b967a45e02"))
    )
    (comp (ref "C265")
      (value "0.1uF_25V_0402")
      (footprint "FP-0402-L_1_0_1-W_0_5_0_1-IPC_C")
      (description "General Purpose Ceramic Capacitor, 0402, 100nF, 10%, X7R, 15%, 25V")
      (fields (field (name "VOLTAGE") "25V") (field (name "TOLERANCE") "10%"))
      (libsource (lib "Altium Content Vault") (part "b4654b650e69147ec39a6b967a45e02"))
    )
    (comp (ref "C267")
      (value "10uF_10V_0402")
      (footprint "FP-CL05A106MP5NUNC-MFG")
      (description "CAP CER 10UF 10V X5R 0402")
      (fields
        (field (name "OCTOPART") "https://octopart.com/cl05a106mp5nunc-samsung-22457395")
        (field (name "TOLERANCE") "20%")
      )
      (libsource (lib "Altium Content Vault") (part "b4654b650e69147ec39a6b967a45e02"))
    )
    (comp (ref "C268")
      (value "0.1uF_25V_0402")
      (footprint "FP-0402-L_1_0_1-W_0_5_0_1-IPC_C")
      (description "General Purpose Ceramic Capacitor, 0402, 100nF, 10%, X7R, 15%, 25V")
      (fields (field (name "VOLTAGE") "25V") (field (name "TOLERANCE") "10%"))
      (libsource (lib "Altium Content Vault") (part "b4654b650e69147ec39a6b967a45e02"))
    )
    (comp (ref "C269")
      (value "10uF_10V_0402")
      (footprint "FP-CL05A106MP5NUNC-MFG")
      (description "CAP CER 10UF 10V X5R 0402")
      (fields
        (field (name "OCTOPART") "https://octopart.com/cl05a106mp5nunc-samsung-22457395")
        (field (name "TOLERANCE") "20%")
      )
      (libsource (lib "Altium Content Vault") (part "b4654b650e69147ec39a6b967a45e02"))
    )
    (comp (ref "C270")
      (value "0.1uF_25V_0402")
      (footprint "FP-0402-L_1_0_1-W_0_5_0_1-IPC_C")
      (description "General Purpose Ceramic Capacitor, 0402, 100nF, 10%, X7R, 15%, 25V")
      (fields (field (name "VOLTAGE") "25V") (field (name "TOLERANCE") "10%"))
      (libsource (lib "Altium Content Vault") (part "b4654b650e69147ec39a6b967a45e02"))
    )
    (comp (ref "C271")
      (value "0.1uF_25V_0402")
      (footprint "FP-0402-L_1_0_1-W_0_5_0_1-IPC_C")
      (description "General Purpose Ceramic Capacitor, 0402, 100nF, 10%, X7R, 15%, 25V")
      (fields (field (name "VOLTAGE") "25V") (field (name "TOLERANCE") "10%"))
      (libsource (lib "Altium Content Vault") (part "b4654b650e69147ec39a6b967a45e02"))
    )
    (comp (ref "C272")
      (value "0.1uF_25V_0402")
      (footprint "FP-0402-L_1_0_1-W_0_5_0_1-IPC_C")
      (description "General Purpose Ceramic Capacitor, 0402, 100nF, 10%, X7R, 15%, 25V")
      (fields (field (name "VOLTAGE") "25V") (field (name "TOLERANCE") "10%"))
      (libsource (lib "Altium Content Vault") (part "b4654b650e69147ec39a6b967a45e02"))
    )
    (comp (ref "C273")
      (value "0.1uF_25V_0402")
      (footprint "FP-0402-L_1_0_1-W_0_5_0_1-IPC_C")
      (description "General Purpose Ceramic Capacitor, 0402, 100nF, 10%, X7R, 15%, 25V")
      (fields (field (name "VOLTAGE") "25V") (field (name "TOLERANCE") "10%"))
      (libsource (lib "Altium Content Vault") (part "b4654b650e69147ec39a6b967a45e02"))
    )
    (comp (ref "L16")
      (value "742792780")
      (footprint "SMD-0402")
      (description "SMD EMI Suppression Ferrite Bead WE-CBF, Z = 220 Ohm")
      (libsource (lib "Altium Content Vault") (part "PAS-IND-INDUCTOR-2"))
    )
    (comp (ref "L20")
      (value "742792780")
      (footprint "SMD-0402")
      (description "SMD EMI Suppression Ferrite Bead WE-CBF, Z = 220 Ohm")
      (libsource (lib "Altium Content Vault") (part "PAS-IND-INDUCTOR-2"))
    )
    (comp (ref "L21")
      (value "742792780")
      (footprint "SMD-0402")
      (description "SMD EMI Suppression Ferrite Bead WE-CBF, Z = 220 Ohm")
      (libsource (lib "Altium Content Vault") (part "PAS-IND-INDUCTOR-2"))
    )
    (comp (ref "L22")
      (value "742792780")
      (footprint "SMD-0402")
      (description "SMD EMI Suppression Ferrite Bead WE-CBF, Z = 220 Ohm")
      (libsource (lib "Altium Content Vault") (part "PAS-IND-INDUCTOR-2"))
    )
    (comp (ref "L23")
      (value "742792780")
      (footprint "SMD-0402")
      (description "SMD EMI Suppression Ferrite Bead WE-CBF, Z = 220 Ohm")
      (libsource (lib "Altium Content Vault") (part "PAS-IND-INDUCTOR-2"))
    )
    (comp (ref "L24")
      (value "742792780")
      (footprint "SMD-0402")
      (description "SMD EMI Suppression Ferrite Bead WE-CBF, Z = 220 Ohm")
      (libsource (lib "Altium Content Vault") (part "PAS-IND-INDUCTOR-2"))
    )
    (comp (ref "L25")
      (value "742792780")
      (footprint "SMD-0402")
      (description "SMD EMI Suppression Ferrite Bead WE-CBF, Z = 220 Ohm")
      (libsource (lib "Altium Content Vault") (part "PAS-IND-INDUCTOR-2"))
    )
    (comp (ref "L26")
      (value "742792780")
      (footprint "SMD-0402")
      (description "SMD EMI Suppression Ferrite Bead WE-CBF, Z = 220 Ohm")
      (libsource (lib "Altium Content Vault") (part "PAS-IND-INDUCTOR-2"))
    )
    (comp (ref "L27")
      (value "742792780")
      (footprint "SMD-0402")
      (description "SMD EMI Suppression Ferrite Bead WE-CBF, Z = 220 Ohm")
      (libsource (lib "Altium Content Vault") (part "PAS-IND-INDUCTOR-2"))
    )
    (comp (ref "L28")
      (value "742792780")
      (footprint "SMD-0402")
      (description "SMD EMI Suppression Ferrite Bead WE-CBF, Z = 220 Ohm")
      (libsource (lib "Altium Content Vault") (part "PAS-IND-INDUCTOR-2"))
    )
    (comp (ref "L29")
      (value "742792780")
      (footprint "SMD-0402")
      (description "SMD EMI Suppression Ferrite Bead WE-CBF, Z = 220 Ohm")
      (libsource (lib "Altium Content Vault") (part "PAS-IND-INDUCTOR-2"))
    )
    (comp (ref "L30")
      (value "742792780")
      (footprint "SMD-0402")
      (description "SMD EMI Suppression Ferrite Bead WE-CBF, Z = 220 Ohm")
      (libsource (lib "Altium Content Vault") (part "PAS-IND-INDUCTOR-2"))
    )
    (comp (ref "L31")
      (value "742792780")
      (footprint "SMD-0402")
      (description "SMD EMI Suppression Ferrite Bead WE-CBF, Z = 220 Ohm")
      (libsource (lib "Altium Content Vault") (part "PAS-IND-INDUCTOR-2"))
    )
    (comp (ref "L32")
      (value "742792780")
      (footprint "SMD-0402")
      (description "SMD EMI Suppression Ferrite Bead WE-CBF, Z = 220 Ohm")
      (libsource (lib "Altium Content Vault") (part "PAS-IND-INDUCTOR-2"))
    )
    (comp (ref "L33")
      (value "742792780")
      (footprint "SMD-0402")
      (description "SMD EMI Suppression Ferrite Bead WE-CBF, Z = 220 Ohm")
      (libsource (lib "Altium Content Vault") (part "PAS-IND-INDUCTOR-2"))
    )
    (comp (ref "L34")
      (value "742792780")
      (footprint "SMD-0402")
      (description "SMD EMI Suppression Ferrite Bead WE-CBF, Z = 220 Ohm")
      (libsource (lib "Altium Content Vault") (part "PAS-IND-INDUCTOR-2"))
    )
    (comp (ref "L35")
      (value "742792780")
      (footprint "SMD-0402")
      (description "SMD EMI Suppression Ferrite Bead WE-CBF, Z = 220 Ohm")
      (libsource (lib "Altium Content Vault") (part "PAS-IND-INDUCTOR-2"))
    )
    (comp (ref "L36")
      (value "742792780")
      (footprint "SMD-0402")
      (description "SMD EMI Suppression Ferrite Bead WE-CBF, Z = 220 Ohm")
      (libsource (lib "Altium Content Vault") (part "PAS-IND-INDUCTOR-2"))
    )
    (comp (ref "L37")
      (value "742792780")
      (footprint "SMD-0402")
      (description "SMD EMI Suppression Ferrite Bead WE-CBF, Z = 220 Ohm")
      (libsource (lib "Altium Content Vault") (part "PAS-IND-INDUCTOR-2"))
    )
    (comp (ref "L38")
      (value "742792780")
      (footprint "SMD-0402")
      (description "SMD EMI Suppression Ferrite Bead WE-CBF, Z = 220 Ohm")
      (libsource (lib "Altium Content Vault") (part "PAS-IND-INDUCTOR-2"))
    )
    (comp (ref "L39")
      (value "742792780")
      (footprint "SMD-0402")
      (description "SMD EMI Suppression Ferrite Bead WE-CBF, Z = 220 Ohm")
      (libsource (lib "Altium Content Vault") (part "PAS-IND-INDUCTOR-2"))
    )
    (comp (ref "L40")
      (value "742792780")
      (footprint "SMD-0402")
      (description "SMD EMI Suppression Ferrite Bead WE-CBF, Z = 220 Ohm")
      (libsource (lib "Altium Content Vault") (part "PAS-IND-INDUCTOR-2"))
    )
    (comp (ref "L41")
      (value "742792780")
      (footprint "SMD-0402")
      (description "SMD EMI Suppression Ferrite Bead WE-CBF, Z = 220 Ohm")
      (libsource (lib "Altium Content Vault") (part "PAS-IND-INDUCTOR-2"))
    )
    (comp (ref "L42")
      (value "742792780")
      (footprint "SMD-0402")
      (description "SMD EMI Suppression Ferrite Bead WE-CBF, Z = 220 Ohm")
      (libsource (lib "Altium Content Vault") (part "PAS-IND-INDUCTOR-2"))
    )
    (comp (ref "L43")
      (value "742792780")
      (footprint "SMD-0402")
      (description "SMD EMI Suppression Ferrite Bead WE-CBF, Z = 220 Ohm")
      (libsource (lib "Altium Content Vault") (part "PAS-IND-INDUCTOR-2"))
    )
    (comp (ref "L44")
      (value "742792780")
      (footprint "SMD-0402")
      (description "SMD EMI Suppression Ferrite Bead WE-CBF, Z = 220 Ohm")
      (libsource (lib "Altium Content Vault") (part "PAS-IND-INDUCTOR-2"))
    )
    (comp (ref "L45")
      (value "742792780")
      (footprint "SMD-0402")
      (description "SMD EMI Suppression Ferrite Bead WE-CBF, Z = 220 Ohm")
      (libsource (lib "Altium Content Vault") (part "PAS-IND-INDUCTOR-2"))
    )
    (comp (ref "L46")
      (value "742792780")
      (footprint "SMD-0402")
      (description "SMD EMI Suppression Ferrite Bead WE-CBF, Z = 220 Ohm")
      (libsource (lib "Altium Content Vault") (part "PAS-IND-INDUCTOR-2"))
    )
    (comp (ref "R87")
      (value "0_5%_0402")
      (footprint "RESC1005X40X25LL10T10")
      (fields (field (name "MANUFACTURER") "KOA Speer") (field (name "PART NUMBER") "RK73Z1ETTP"))
      (libsource (lib "Altium Content Vault") (part "RES"))
    )
    (comp (ref "R88")
      (value "0_5%_0402")
      (footprint "RESC1005X40X25LL10T10")
      (fields (field (name "MANUFACTURER") "KOA Speer") (field (name "PART NUMBER") "RK73Z1ETTP"))
      (libsource (lib "Altium Content Vault") (part "RES"))
    )
    (comp (ref "R92")
      (value "100_1%_0402")
      (footprint "RESC1005X40X25ML05T10")
      (fields (field (name "PART NUMBER") "ERJ-U02F1000X") (field (name "MANUFACTURER") "Panasonic"))
      (libsource (lib "Altium Content Vault") (part "RES"))
    )
    (comp (ref "R93")
      (value "49.9_1%_0402")
      (footprint "RESC1005X40X25NL10T10")
      (fields (field (name "PART NUMBER") "RK73H1ETTP49R9F") (field (name "MANUFACTURER") "KOA Speer"))
      (libsource (lib "Altium Content Vault") (part "RES"))
    )
    (comp (ref "R100")
      (value "100_1%_0402")
      (footprint "RESC1005X40X25ML05T10")
      (fields (field (name "PART NUMBER") "ERJ-U02F1000X") (field (name "MANUFACTURER") "Panasonic"))
      (libsource (lib "Altium Content Vault") (part "RES"))
    )
    (comp (ref "Y5")
      (value "SIT5001AC-3E-33N0-40.000000X")
      (footprint "FP-SiT5001-3-MFG")
      (description "MEMS OSC TCXO 40.0000MHZ LVCMOS")
      (libsource (lib "Altium Content Vault") (part "f2b4964c30f19ad016f2c5313c7e3e3"))
    )
  )
  (nets
    (net (code "1") (name "DPLL_OSCI") (class "Default")
      (node (ref "C271") (pin "2") (pinfunction "2_2") (pintype "passive"))
    )
    (net (code "2") (name "DPLL_VDDA_BG_LC") (class "Default")
      (node (ref "C145") (pin "1") (pinfunction "1_1") (pintype "passive"))
      (node (ref "C146") (pin "1") (pinfunction "1_1") (pintype "passive"))
      (node (ref "C147") (pin "1") (pinfunction "1_1") (pintype "passive"))
      (node (ref "L20") (pin "2") (pinfunction "2_2") (pintype "passive"))
    )
    (net (code "3") (name "DPLL_VDDA_FB") (class "Default")
      (node (ref "C228") (pin "1") (pinfunction "1_1") (pintype "passive"))
      (node (ref "C229") (pin "1") (pinfunction "1_1") (pintype "passive"))
      (node (ref "L36") (pin "2") (pinfunction "2_2") (pintype "passive"))
    )
    (net (code "4") (name "DPLL_VDDA_PDCP_XTAL") (class "Default")
      (node (ref "C171") (pin "1") (pinfunction "1_1") (pintype "passive"))
      (node (ref "C177") (pin "1") (pinfunction "1_1") (pintype "passive"))
      (node (ref "L26") (pin "2") (pinfunction "2_2") (pintype "passive"))
    )
    (net (code "5") (name "DPLL_VDDO_Q0") (class "Default")
      (node (ref "C211") (pin "1") (pinfunction "1_1") (pintype "passive"))
      (node (ref "C212") (pin "1") (pinfunction "1_1") (pintype "passive"))
      (node (ref "L30") (pin "2") (pinfunction "2_2") (pintype "passive"))
    )
    (net (code "6") (name "DPLL_VDDO_Q1") (class "Default")
      (node (ref "C232") (pin "1") (pinfunction "1_1") (pintype "passive"))
      (node (ref "C233") (pin "1") (pinfunction "1_1") (pintype "passive"))
      (node (ref "L35") (pin "2") (pinfunction "2_2") (pintype "passive"))
    )
    (net (code "7") (name "DPLL_VDDO_Q2") (class "Default")
      (node (ref "C242") (pin "1") (pinfunction "1_1") (pintype "passive"))
      (node (ref "C243") (pin "1") (pinfunction "1_1") (pintype "passive"))
      (node (ref "L39") (pin "2") (pinfunction "2_2") (pintype "passive"))
    )
    (net (code "8") (name "DPLL_VDDO_Q3") (class "Default")
      (node (ref "C252") (pin "1") (pinfunction "1_1") (pintype "passive"))
      (node (ref "C253") (pin "1") (pinfunction "1_1") (pintype "passive"))
      (node (ref "L42") (pin "2") (pinfunction "2_2") (pintype "passive"))
    )
    (net (code "9") (name "DPLL_VDDO_Q4") (class "Default")
      (node (ref "C107") (pin "1") (pinfunction "1_1") (pintype "passive"))
      (node (ref "C122") (pin "1") (pinfunction "1_1") (pintype "passive"))
      (node (ref "L16") (pin "2") (pinfunction "2_2") (pintype "passive"))
    )
    (net (code "10") (name "DPLL_VDDO_Q5") (class "Default")
      (node (ref "C163") (pin "1") (pinfunction "1_1") (pintype "passive"))
      (node (ref "C164") (pin "1") (pinfunction "1_1") (pintype "passive"))
      (node (ref "L23") (pin "2") (pinfunction "2_2") (pintype "passive"))
    )
    (net (code "11") (name "DPLL_VDDO_Q6") (class "Default")
      (node (ref "C206") (pin "1") (pinfunction "1_1") (pintype "passive"))
      (node (ref "C207") (pin "1") (pinfunction "1_1") (pintype "passive"))
      (node (ref "L29") (pin "2") (pinfunction "2_2") (pintype "passive"))
    )
    (net (code "12") (name "DPLL_VDDO_Q7") (class "Default")
      (node (ref "C224") (pin "1") (pinfunction "1_1") (pintype "passive"))
      (node (ref "C225") (pin "1") (pinfunction "1_1") (pintype "passive"))
      (node (ref "L34") (pin "2") (pinfunction "2_2") (pintype "passive"))
    )
    (net (code "13") (name "DPLL_VDDO_Q8") (class "Default")
      (node (ref "C248") (pin "1") (pinfunction "1_1") (pintype "passive"))
      (node (ref "C249") (pin "1") (pinfunction "1_1") (pintype "passive"))
      (node (ref "L41") (pin "2") (pinfunction "2_2") (pintype "passive"))
    )
    (net (code "14") (name "DPLL_VDDO_Q9") (class "Default")
      (node (ref "C256") (pin "1") (pinfunction "1_1") (pintype "passive"))
      (node (ref "C257") (pin "1") (pinfunction "1_1") (pintype "passive"))
      (node (ref "L43") (pin "2") (pinfunction "2_2") (pintype "passive"))
    )
    (net (code "15") (name "DPLL_VDDO_Q10") (class "Default")
      (node (ref "C264") (pin "1") (pinfunction "1_1") (pintype "passive"))
      (node (ref "C265") (pin "1") (pinfunction "1_1") (pintype "passive"))
      (node (ref "L45") (pin "2") (pinfunction "2_2") (pintype "passive"))
    )
    (net (code "16") (name "DPLL_VDDO_Q11") (class "Default")
      (node (ref "C262") (pin "1") (pinfunction "1_1") (pintype "passive"))
      (node (ref "C263") (pin "1") (pinfunction "1_1") (pintype "passive"))
      (node (ref "L44") (pin "2") (pinfunction "2_2") (pintype "passive"))
    )
    (net (code "17") (name "DPLL_VDD_CLKA") (class "Default")
      (node (ref "C238") (pin "1") (pinfunction "1_1") (pintype "passive"))
      (node (ref "C239") (pin "1") (pinfunction "1_1") (pintype "passive"))
      (node (ref "L38") (pin "2") (pinfunction "2_2") (pintype "passive"))
    )
    (net (code "18") (name "DPLL_VDD_CLKB") (class "Default")
      (node (ref "C219") (pin "1") (pinfunction "1_1") (pintype "passive"))
      (node (ref "C220") (pin "1") (pinfunction "1_1") (pintype "passive"))
      (node (ref "L33") (pin "2") (pinfunction "2_2") (pintype "passive"))
    )
    (net (code "19") (name "DPLL_VDD_DCO_Q01") (class "Default")
      (node (ref "C179") (pin "1") (pinfunction "1_1") (pintype "passive"))
      (node (ref "C180") (pin "1") (pinfunction "1_1") (pintype "passive"))
      (node (ref "L27") (pin "2") (pinfunction "2_2") (pintype "passive"))
    )
    (net (code "20") (name "DPLL_VDD_DCO_Q8") (class "Default")
      (node (ref "C181") (pin "1") (pinfunction "1_1") (pintype "passive"))
      (node (ref "C182") (pin "1") (pinfunction "1_1") (pintype "passive"))
      (node (ref "L28") (pin "2") (pinfunction "2_2") (pintype "passive"))
    )
    (net (code "21") (name "DPLL_VDD_DCO_Q9") (class "Default")
      (node (ref "C215") (pin "1") (pinfunction "1_1") (pintype "passive"))
      (node (ref "C216") (pin "1") (pinfunction "1_1") (pintype "passive"))
      (node (ref "L32") (pin "2") (pinfunction "2_2") (pintype "passive"))
    )
    (net (code "22") (name "DPLL_VDD_DCO_Q10") (class "Default")
      (node (ref "C230") (pin "1") (pinfunction "1_1") (pintype "passive"))
      (node (ref "C231") (pin "1") (pinfunction "1_1") (pintype "passive"))
      (node (ref "L37") (pin "2") (pinfunction "2_2") (pintype "passive"))
    )
    (net (code "23") (name "DPLL_VDD_DCO_Q11") (class "Default")
      (node (ref "C240") (pin "1") (pinfunction "1_1") (pintype "passive"))
      (node (ref "C241") (pin "1") (pinfunction "1_1") (pintype "passive"))
      (node (ref "L40") (pin "2") (pinfunction "2_2") (pintype "passive"))
    )
    (net (code "24") (name "DPLL_VDD_DCO_Q23") (class "Default")
      (node (ref "C213") (pin "1") (pinfunction "1_1") (pintype "passive"))
      (node (ref "C214") (pin "1") (pinfunction "1_1") (pintype "passive"))
      (node (ref "L31") (pin "2") (pinfunction "2_2") (pintype "passive"))
    )
    (net (code "25") (name "DPLL_VDD_DCO_Q45") (class "Default")
      (node (ref "C136") (pin "1") (pinfunction "1_1") (pintype "passive"))
      (node (ref "C137") (pin "1") (pinfunction "1_1") (pintype "passive"))
      (node (ref "L22") (pin "2") (pinfunction "2_2") (pintype "passive"))
    )
    (net (code "26") (name "DPLL_VDD_DCO_Q67") (class "Default")
      (node (ref "C161") (pin "1") (pinfunction "1_1") (pintype "passive"))
      (node (ref "C162") (pin "1") (pinfunction "1_1") (pintype "passive"))
      (node (ref "L25") (pin "2") (pinfunction "2_2") (pintype "passive"))
    )
    (net (code "27") (name "DPLL_VDD_DIA_A") (class "Default")
      (node (ref "C123") (pin "1") (pinfunction "1_1") (pintype "passive"))
      (node (ref "C124") (pin "1") (pinfunction "1_1") (pintype "passive"))
      (node (ref "L21") (pin "2") (pinfunction "2_2") (pintype "passive"))
    )
    (net (code "28") (name "DPLL_VDD_DIA_B") (class "Default")
      (node (ref "C159") (pin "1") (pinfunction "1_1") (pintype "passive"))
      (node (ref "C160") (pin "1") (pinfunction "1_1") (pintype "passive"))
      (node (ref "L24") (pin "2") (pinfunction "2_2") (pintype "passive"))
    )
    (net (code "29") (name "DPLL_VDD_DIG") (class "Default")
      (node (ref "C138") (pin "1") (pinfunction "1_1") (pintype "passive"))
      (node (ref "C139") (pin "1") (pinfunction "1_1") (pintype "passive"))
      (node (ref "C140") (pin "1") (pinfunction "1_1") (pintype "passive"))
      (node (ref "C144") (pin "1") (pinfunction "1_1") (pintype "passive"))
      (node (ref "R87") (pin "2") (pinfunction "2_2") (pintype "passive"))
    )
    (net (code "30") (name "DPLL_VDD_GPIO") (class "Default")
      (node (ref "C167") (pin "1") (pinfunction "1_1") (pintype "passive"))
      (node (ref "C168") (pin "1") (pinfunction "1_1") (pintype "passive"))
      (node (ref "C169") (pin "1") (pinfunction "1_1") (pintype "passive"))
      (node (ref "C170") (pin "1") (pinfunction "1_1") (pintype "passive"))
      (node (ref "R88") (pin "2") (pinfunction "2_2") (pintype "passive"))
    )
    (net (code "31") (name "GND") (class "Default")
      (node (ref "C104") (pin "2") (pinfunction "2_2") (pintype "passive"))
      (node (ref "C106") (pin "2") (pinfunction "2_2") (pintype "passive"))
      (node (ref "C107") (pin "2") (pinfunction "2_2") (pintype "passive"))
      (node (ref "C122") (pin "2") (pinfunction "2_2") (pintype "passive"))
      (node (ref "C123") (pin "2") (pinfunction "2_2") (pintype "passive"))
      (node (ref "C124") (pin "2") (pinfunction "2_2") (pintype "passive"))
      (node (ref "C136") (pin "2") (pinfunction "2_2") (pintype "passive"))
      (node (ref "C137") (pin "2") (pinfunction "2_2") (pintype "passive"))
      (node (ref "C138") (pin "2") (pinfunction "2_2") (pintype "passive"))
      (node (ref "C139") (pin "2") (pinfunction "2_2") (pintype "passive"))
      (node (ref "C140") (pin "2") (pinfunction "2_2") (pintype "passive"))
      (node (ref "C144") (pin "2") (pinfunction "2_2") (pintype "passive"))
      (node (ref "C145") (pin "2") (pinfunction "2_2") (pintype "passive"))
      (node (ref "C146") (pin "2") (pinfunction "2_2") (pintype "passive"))
      (node (ref "C147") (pin "2") (pinfunction "2_2") (pintype "passive"))
      (node (ref "C148") (pin "2") (pinfunction "2_2") (pintype "passive"))
      (node (ref "C149") (pin "2") (pinfunction "2_2") (pintype "passive"))
      (node (ref "C150") (pin "2") (pinfunction "2_2") (pintype "passive"))
      (node (ref "C151") (pin "2") (pinfunction "2_2") (pintype "passive"))
      (node (ref "C152") (pin "2") (pinfunction "2_2") (pintype "passive"))
      (node (ref "C153") (pin "2") (pinfunction "2_2") (pintype "passive"))
      (node (ref "C154") (pin "2") (pinfunction "2_2") (pintype "passive"))
      (node (ref "C155") (pin "2") (pinfunction "2_2") (pintype "passive"))
      (node (ref "C156") (pin "2") (pinfunction "2_2") (pintype "passive"))
      (node (ref "C157") (pin "2") (pinfunction "2_2") (pintype "passive"))
      (node (ref "C158") (pin "2") (pinfunction "2_2") (pintype "passive"))
      (node (ref "C159") (pin "2") (pinfunction "2_2") (pintype "passive"))
      (node (ref "C160") (pin "2") (pinfunction "2_2") (pintype "passive"))
      (node (ref "C161") (pin "2") (pinfunction "2_2") (pintype "passive"))
      (node (ref "C162") (pin "2") (pinfunction "2_2") (pintype "passive"))
      (node (ref "C163") (pin "2") (pinfunction "2_2") (pintype "passive"))
      (node (ref "C164") (pin "2") (pinfunction "2_2") (pintype "passive"))
      (node (ref "C165") (pin "2") (pinfunction "2_2") (pintype "passive"))
      (node (ref "C166") (pin "2") (pinfunction "2_2") (pintype "passive"))
      (node (ref "C167") (pin "2") (pinfunction "2_2") (pintype "passive"))
      (node (ref "C168") (pin "2") (pinfunction "2_2") (pintype "passive"))
      (node (ref "C169") (pin "2") (pinfunction "2_2") (pintype "passive"))
      (node (ref "C170") (pin "2") (pinfunction "2_2") (pintype "passive"))
      (node (ref "C171") (pin "2") (pinfunction "2_2") (pintype "passive"))
      (node (ref "C177") (pin "2") (pinfunction "2_2") (pintype "passive"))
      (node (ref "C178") (pin "2") (pinfunction "2_2") (pintype "passive"))
      (node (ref "C179") (pin "2") (pinfunction "2_2") (pintype "passive"))
      (node (ref "C180") (pin "2") (pinfunction "2_2") (pintype "passive"))
      (node (ref "C181") (pin "2") (pinfunction "2_2") (pintype "passive"))
      (node (ref "C182") (pin "2") (pinfunction "2_2") (pintype "passive"))
      (node (ref "C183") (pin "2") (pinfunction "2_2") (pintype "passive"))
      (node (ref "C203") (pin "2") (pinfunction "2_2") (pintype "passive"))
      (node (ref "C204") (pin "2") (pinfunction "2_2") (pintype "passive"))
      (node (ref "C205") (pin "2") (pinfunction "2_2") (pintype "passive"))
      (node (ref "C206") (pin "2") (pinfunction "2_2") (pintype "passive"))
      (node (ref "C207") (pin "2") (pinfunction "2_2") (pintype "passive"))
      (node (ref "C209") (pin "2") (pinfunction "2_2") (pintype "passive"))
      (node (ref "C210") (pin "2") (pinfunction "2_2") (pintype "passive"))
      (node (ref "C211") (pin "2") (pinfunction "2_2") (pintype "passive"))
      (node (ref "C212") (pin "2") (pinfunction "2_2") (pintype "passive"))
      (node (ref "C213") (pin "2") (pinfunction "2_2") (pintype "passive"))
      (node (ref "C214") (pin "2") (pinfunction "2_2") (pintype "passive"))
      (node (ref "C215") (pin "2") (pinfunction "2_2") (pintype "passive"))
      (node (ref "C216") (pin "2") (pinfunction "2_2") (pintype "passive"))
      (node (ref "C217") (pin "2") (pinfunction "2_2") (pintype "passive"))
      (node (ref "C218") (pin "2") (pinfunction "2_2") (pintype "passive"))
      (node (ref "C219") (pin "2") (pinfunction "2_2") (pintype "passive"))
      (node (ref "C220") (pin "2") (pinfunction "2_2") (pintype "passive"))
      (node (ref "C221") (pin "2") (pinfunction "2_2") (pintype "passive"))
      (node (ref "C222") (pin "2") (pinfunction "2_2") (pintype "passive"))
      (node (ref "C223") (pin "2") (pinfunction "2_2") (pintype "passive"))
      (node (ref "C224") (pin "2") (pinfunction "2_2") (pintype "passive"))
      (node (ref "C225") (pin "2") (pinfunction "2_2") (pintype "passive"))
      (node (ref "C226") (pin "2") (pinfunction "2_2") (pintype "passive"))
      (node (ref "C227") (pin "2") (pinfunction "2_2") (pintype "passive"))
      (node (ref "C228") (pin "2") (pinfunction "2_2") (pintype "passive"))
      (node (ref "C229") (pin "2") (pinfunction "2_2") (pintype "passive"))
      (node (ref "C230") (pin "2") (pinfunction "2_2") (pintype "passive"))
      (node (ref "C231") (pin "2") (pinfunction "2_2") (pintype "passive"))
      (node (ref "C232") (pin "2") (pinfunction "2_2") (pintype "passive"))
      (node (ref "C233") (pin "2") (pinfunction "2_2") (pintype "passive"))
      (node (ref "C234") (pin "2") (pinfunction "2_2") (pintype "passive"))
      (node (ref "C235") (pin "2") (pinfunction "2_2") (pintype "passive"))
      (node (ref "C236") (pin "2") (pinfunction "2_2") (pintype "passive"))
      (node (ref "C237") (pin "2") (pinfunction "2_2") (pintype "passive"))
      (node (ref "C238") (pin "2") (pinfunction "2_2") (pintype "passive"))
      (node (ref "C239") (pin "2") (pinfunction "2_2") (pintype "passive"))
      (node (ref "C240") (pin "2") (pinfunction "2_2") (pintype "passive"))
      (node (ref "C241") (pin "2") (pinfunction "2_2") (pintype "passive"))
      (node (ref "C242") (pin "2") (pinfunction "2_2") (pintype "passive"))
      (node (ref "C243") (pin "2") (pinfunction "2_2") (pintype "passive"))
      (node (ref "C244") (pin "2") (pinfunction "2_2") (pintype "passive"))
      (node (ref "C245") (pin "2") (pinfunction "2_2") (pintype "passive"))
      (node (ref "C246") (pin "2") (pinfunction "2_2") (pintype "passive"))
      (node (ref "C247") (pin "2") (pinfunction "2_2") (pintype "passive"))
      (node (ref "C248") (pin "2") (pinfunction "2_2") (pintype "passive"))
      (node (ref "C249") (pin "2") (pinfunction "2_2") (pintype "passive"))
      (node (ref "C250") (pin "2") (pinfunction "2_2") (pintype "passive"))
      (node (ref "C251") (pin "2") (pinfunction "2_2") (pintype "passive"))
      (node (ref "C252") (pin "2") (pinfunction "2_2") (pintype "passive"))
      (node (ref "C253") (pin "2") (pinfunction "2_2") (pintype "passive"))
      (node (ref "C254") (pin "2") (pinfunction "2_2") (pintype "passive"))
      (node (ref "C255") (pin "2") (pinfunction "2_2") (pintype "passive"))
      (node (ref "C256") (pin "2") (pinfunction "2_2") (pintype "passive"))
      (node (ref "C257") (pin "2") (pinfunction "2_2") (pintype "passive"))
      (node (ref "C258") (pin "2") (pinfunction "2_2") (pintype "passive"))
      (node (ref "C259") (pin "2") (pinfunction "2_2") (pintype "passive"))
      (node (ref "C260") (pin "2") (pinfunction "2_2") (pintype "passive"))
      (node (ref "C261") (pin "2") (pinfunction "2_2") (pintype "passive"))
      (node (ref "C262") (pin "2") (pinfunction "2_2") (pintype "passive"))
      (node (ref "C263") (pin "2") (pinfunction "2_2") (pintype "passive"))
      (node (ref "C264") (pin "2") (pinfunction "2_2") (pintype "passive"))
      (node (ref "C265") (pin "2") (pinfunction "2_2") (pintype "passive"))
      (node (ref "C267") (pin "2") (pinfunction "2_2") (pintype "passive"))
      (node (ref "C268") (pin "2") (pinfunction "2_2") (pintype "passive"))
      (node (ref "C269") (pin "2") (pinfunction "2_2") (pintype "passive"))
      (node (ref "C270") (pin "2") (pinfunction "2_2") (pintype "passive"))
      (node (ref "C272") (pin "2") (pinfunction "2_2") (pintype "passive"))
      (node (ref "C273") (pin "2") (pinfunction "2_2") (pintype "passive"))
      (node (ref "R100") (pin "1") (pinfunction "1_1") (pintype "passive"))
      (node (ref "Y5") (pin "2") (pinfunction "GND_2") (pintype "power_in"))
    )
    (net (code "32") (name "Net-(C271-Pad1)") (class "Default")
      (node (ref "C271") (pin "1") (pinfunction "1_1") (pintype "passive"))
      (node (ref "R100") (pin "2") (pinfunction "2_2") (pintype "passive"))
      (node (ref "R92") (pin "1") (pinfunction "1_1") (pintype "passive"))
      (node (ref "R93") (pin "2") (pinfunction "2_2") (pintype "passive"))
    )
    (net (code "33") (name "Net-(Y5-OUT)") (class "Default")
      (node (ref "R93") (pin "1") (pinfunction "1_1") (pintype "passive"))
      (node (ref "Y5") (pin "3") (pinfunction "OUT_3") (pintype "output"))
    )
    (net (code "34") (name "Net-(Y5-VDD)") (class "Default")
      (node (ref "C269") (pin "1") (pinfunction "1_1") (pintype "passive"))
      (node (ref "C270") (pin "1") (pinfunction "1_1") (pintype "passive"))
      (node (ref "C272") (pin "1") (pinfunction "1_1") (pintype "passive"))
      (node (ref "C273") (pin "1") (pinfunction "1_1") (pintype "passive"))
      (node (ref "L46") (pin "2") (pinfunction "2_2") (pintype "passive"))
      (node (ref "Y5") (pin "4") (pinfunction "VDD_4") (pintype "power_in"))
    )
    (net (code "35") (name "P1V8") (class "Default")
      (node (ref "C104") (pin "1") (pinfunction "1_1") (pintype "passive"))
      (node (ref "C106") (pin "1") (pinfunction "1_1") (pintype "passive"))
      (node (ref "C150") (pin "1") (pinfunction "1_1") (pintype "passive"))
      (node (ref "C151") (pin "1") (pinfunction "1_1") (pintype "passive"))
      (node (ref "C152") (pin "1") (pinfunction "1_1") (pintype "passive"))
      (node (ref "C153") (pin "1") (pinfunction "1_1") (pintype "passive"))
      (node (ref "C154") (pin "1") (pinfunction "1_1") (pintype "passive"))
      (node (ref "C155") (pin "1") (pinfunction "1_1") (pintype "passive"))
      (node (ref "C165") (pin "1") (pinfunction "1_1") (pintype "passive"))
      (node (ref "C166") (pin "1") (pinfunction "1_1") (pintype "passive"))
      (node (ref "C183") (pin "1") (pinfunction "1_1") (pintype "passive"))
      (node (ref "C203") (pin "1") (pinfunction "1_1") (pintype "passive"))
      (node (ref "C217") (pin "1") (pinfunction "1_1") (pintype "passive"))
      (node (ref "C218") (pin "1") (pinfunction "1_1") (pintype "passive"))
      (node (ref "C226") (pin "1") (pinfunction "1_1") (pintype "passive"))
      (node (ref "C227") (pin "1") (pinfunction "1_1") (pintype "passive"))
      (node (ref "C234") (pin "1") (pinfunction "1_1") (pintype "passive"))
      (node (ref "C235") (pin "1") (pinfunction "1_1") (pintype "passive"))
      (node (ref "C245") (pin "1") (pinfunction "1_1") (pintype "passive"))
      (node (ref "C250") (pin "1") (pinfunction "1_1") (pintype "passive"))
      (node (ref "C251") (pin "1") (pinfunction "1_1") (pintype "passive"))
      (node (ref "L16") (pin "1") (pinfunction "1_1") (pintype "passive"))
      (node (ref "L21") (pin "1") (pinfunction "1_1") (pintype "passive"))
      (node (ref "L22") (pin "1") (pinfunction "1_1") (pintype "passive"))
      (node (ref "L24") (pin "1") (pinfunction "1_1") (pintype "passive"))
      (node (ref "L25") (pin "1") (pinfunction "1_1") (pintype "passive"))
      (node (ref "L27") (pin "1") (pinfunction "1_1") (pintype "passive"))
      (node (ref "L28") (pin "1") (pinfunction "1_1") (pintype "passive"))
      (node (ref "L31") (pin "1") (pinfunction "1_1") (pintype "passive"))
      (node (ref "L32") (pin "1") (pinfunction "1_1") (pintype "passive"))
      (node (ref "L35") (pin "1") (pinfunction "1_1") (pintype "passive"))
      (node (ref "L36") (pin "1") (pinfunction "1_1") (pintype "passive"))
      (node (ref "L37") (pin "1") (pinfunction "1_1") (pintype "passive"))
      (node (ref "L40") (pin "1") (pinfunction "1_1") (pintype "passive"))
      (node (ref "L42") (pin "1") (pinfunction "1_1") (pintype "passive"))
      (node (ref "R87") (pin "1") (pinfunction "1_1") (pintype "passive"))
    )
    (net (code "36") (name "P3V3") (class "Default")
      (node (ref "C148") (pin "1") (pinfunction "1_1") (pintype "passive"))
      (node (ref "C149") (pin "1") (pinfunction "1_1") (pintype "passive"))
      (node (ref "C156") (pin "1") (pinfunction "1_1") (pintype "passive"))
      (node (ref "C157") (pin "1") (pinfunction "1_1") (pintype "passive"))
      (node (ref "C158") (pin "1") (pinfunction "1_1") (pintype "passive"))
      (node (ref "C178") (pin "1") (pinfunction "1_1") (pintype "passive"))
      (node (ref "C204") (pin "1") (pinfunction "1_1") (pintype "passive"))
      (node (ref "C205") (pin "1") (pinfunction "1_1") (pintype "passive"))
      (node (ref "C209") (pin "1") (pinfunction "1_1") (pintype "passive"))
      (node (ref "C210") (pin "1") (pinfunction "1_1") (pintype "passive"))
      (node (ref "C221") (pin "1") (pinfunction "1_1") (pintype "passive"))
      (node (ref "C222") (pin "1") (pinfunction "1_1") (pintype "passive"))
      (node (ref "C223") (pin "1") (pinfunction "1_1") (pintype "passive"))
      (node (ref "C236") (pin "1") (pinfunction "1_1") (pintype "passive"))
      (node (ref "C237") (pin "1") (pinfunction "1_1") (pintype "passive"))
      (node (ref "C244") (pin "1") (pinfunction "1_1") (pintype "passive"))
      (node (ref "C246") (pin "1") (pinfunction "1_1") (pintype "passive"))
      (node (ref "C247") (pin "1") (pinfunction "1_1") (pintype "passive"))
      (node (ref "C254") (pin "1") (pinfunction "1_1") (pintype "passive"))
      (node (ref "C255") (pin "1") (pinfunction "1_1") (pintype "passive"))
      (node (ref "C258") (pin "1") (pinfunction "1_1") (pintype "passive"))
      (node (ref "C259") (pin "1") (pinfunction "1_1") (pintype "passive"))
      (node (ref "C260") (pin "1") (pinfunction "1_1") (pintype "passive"))
      (node (ref "C261") (pin "1") (pinfunction "1_1") (pintype "passive"))
      (node (ref "C267") (pin "1") (pinfunction "1_1") (pintype "passive"))
      (node (ref "C268") (pin "1") (pinfunction "1_1") (pintype "passive"))
      (node (ref "L20") (pin "1") (pinfunction "1_1") (pintype "passive"))
      (node (ref "L23") (pin "1") (pinfunction "1_1") (pintype "passive"))
      (node (ref "L26") (pin "1") (pinfunction "1_1") (pintype "passive"))
      (node (ref "L29") (pin "1") (pinfunction "1_1") (pintype "passive"))
      (node (ref "L30") (pin "1") (pinfunction "1_1") (pintype "passive"))
      (node (ref "L33") (pin "1") (pinfunction "1_1") (pintype "passive"))
      (node (ref "L34") (pin "1") (pinfunction "1_1") (pintype "passive"))
      (node (ref "L38") (pin "1") (pinfunction "1_1") (pintype "passive"))
      (node (ref "L39") (pin "1") (pinfunction "1_1") (pintype "passive"))
      (node (ref "L41") (pin "1") (pinfunction "1_1") (pintype "passive"))
      (node (ref "L43") (pin "1") (pinfunction "1_1") (pintype "passive"))
      (node (ref "L44") (pin "1") (pinfunction "1_1") (pintype "passive"))
      (node (ref "L45") (pin "1") (pinfunction "1_1") (pintype "passive"))
      (node (ref "L46") (pin "1") (pinfunction "1_1") (pintype "passive"))
      (node (ref "R88") (pin "1") (pinfunction "1_1") (pintype "passive"))
      (node (ref "R92") (pin "2") (pinfunction "2_2") (pintype "passive"))
    )
    (net (code "37") (name "unconnected-(Y5-NC-Pad1)") (class "Default")
      (node (ref "Y5") (pin "1") (pinfunction "NC_1") (pintype "passive"))
    )
  )
)
